# Clock_1.net
KiCad netlist of a schematic drawn in EAGLE
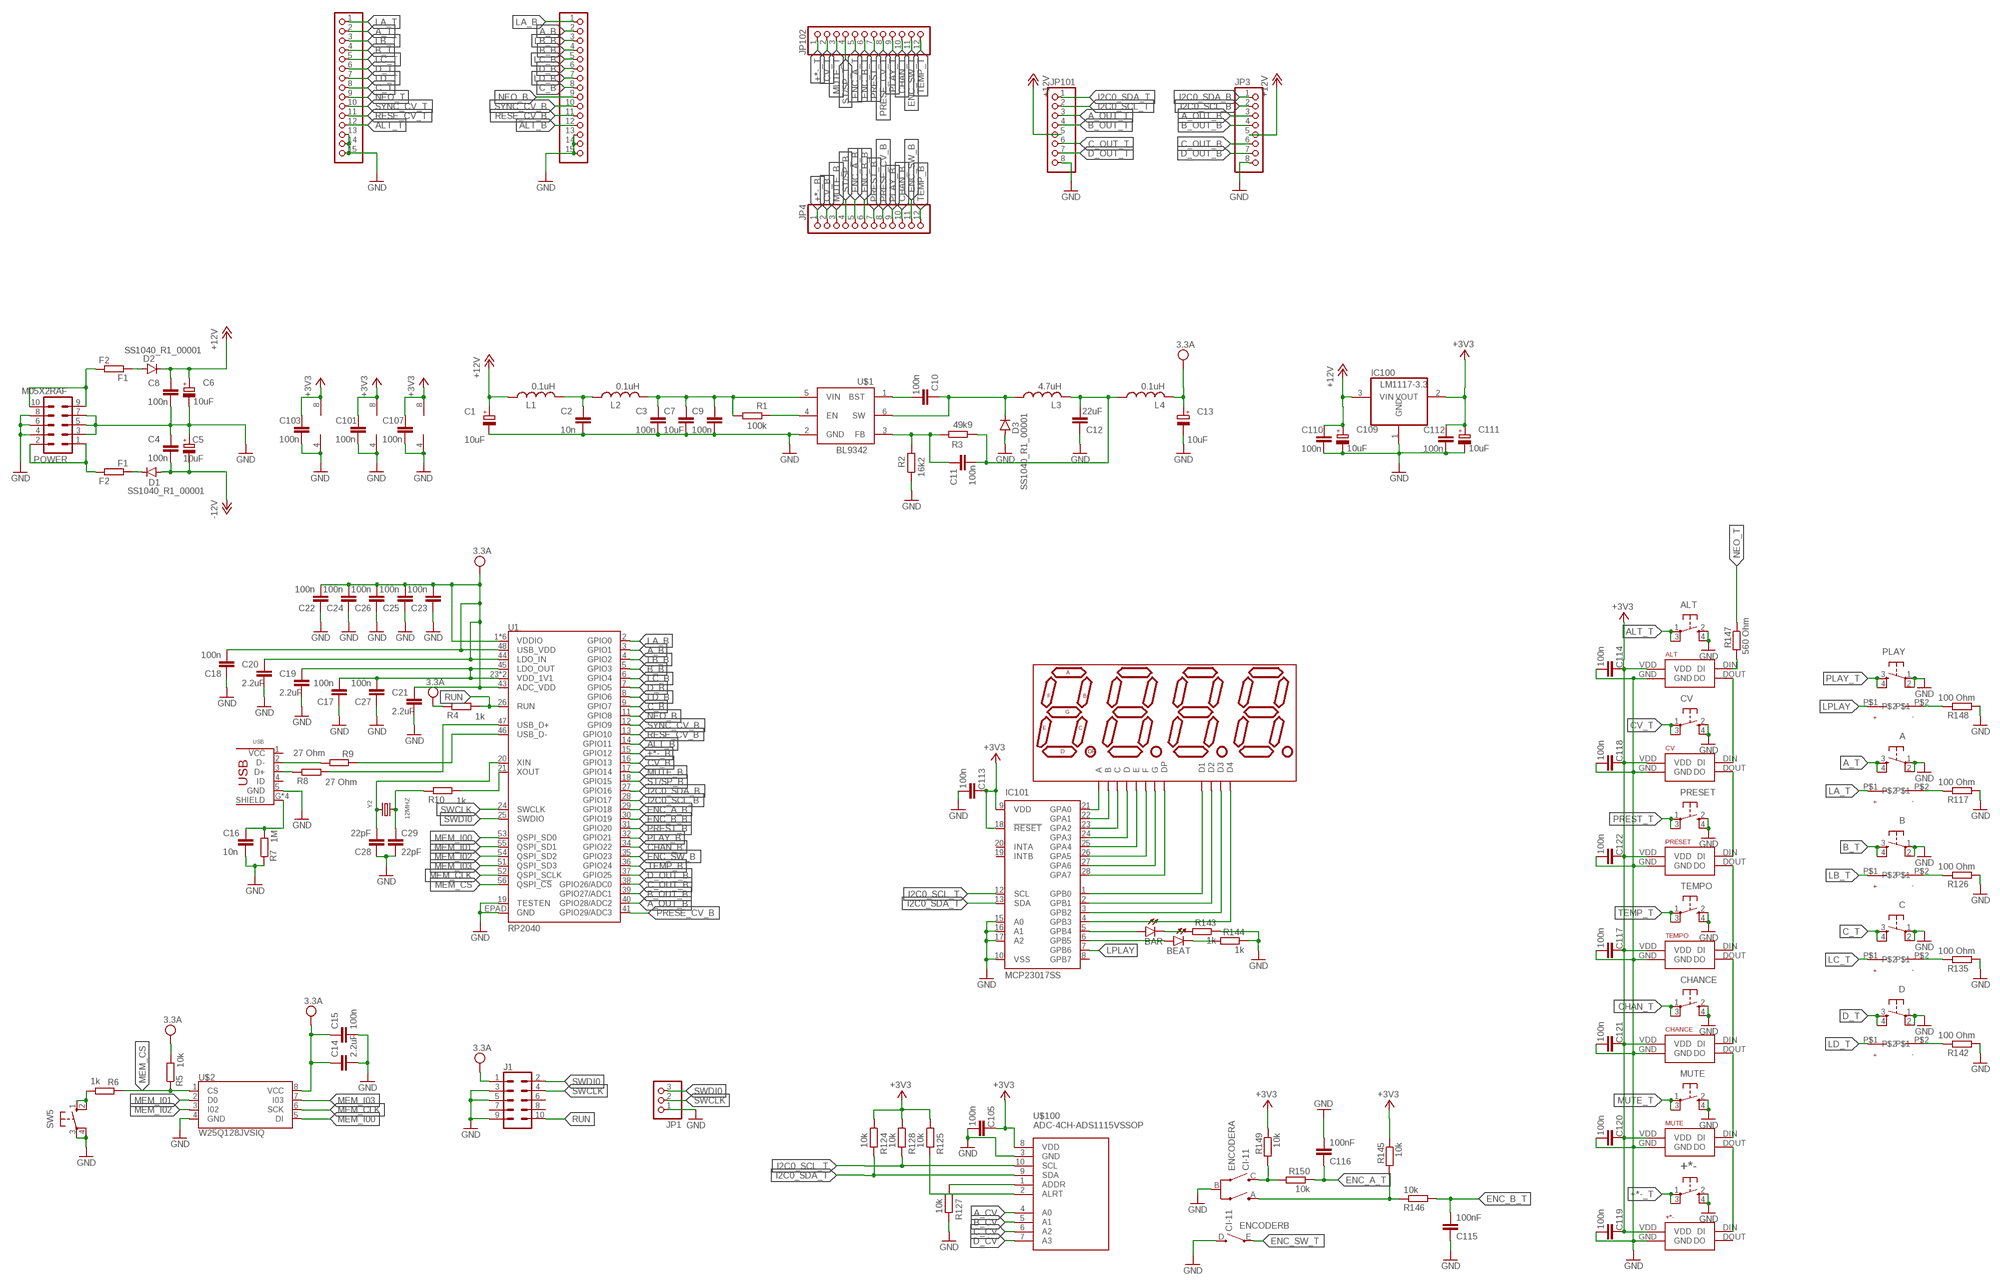
[diagram p0: schematic, sheet 1, part 1 of 2]
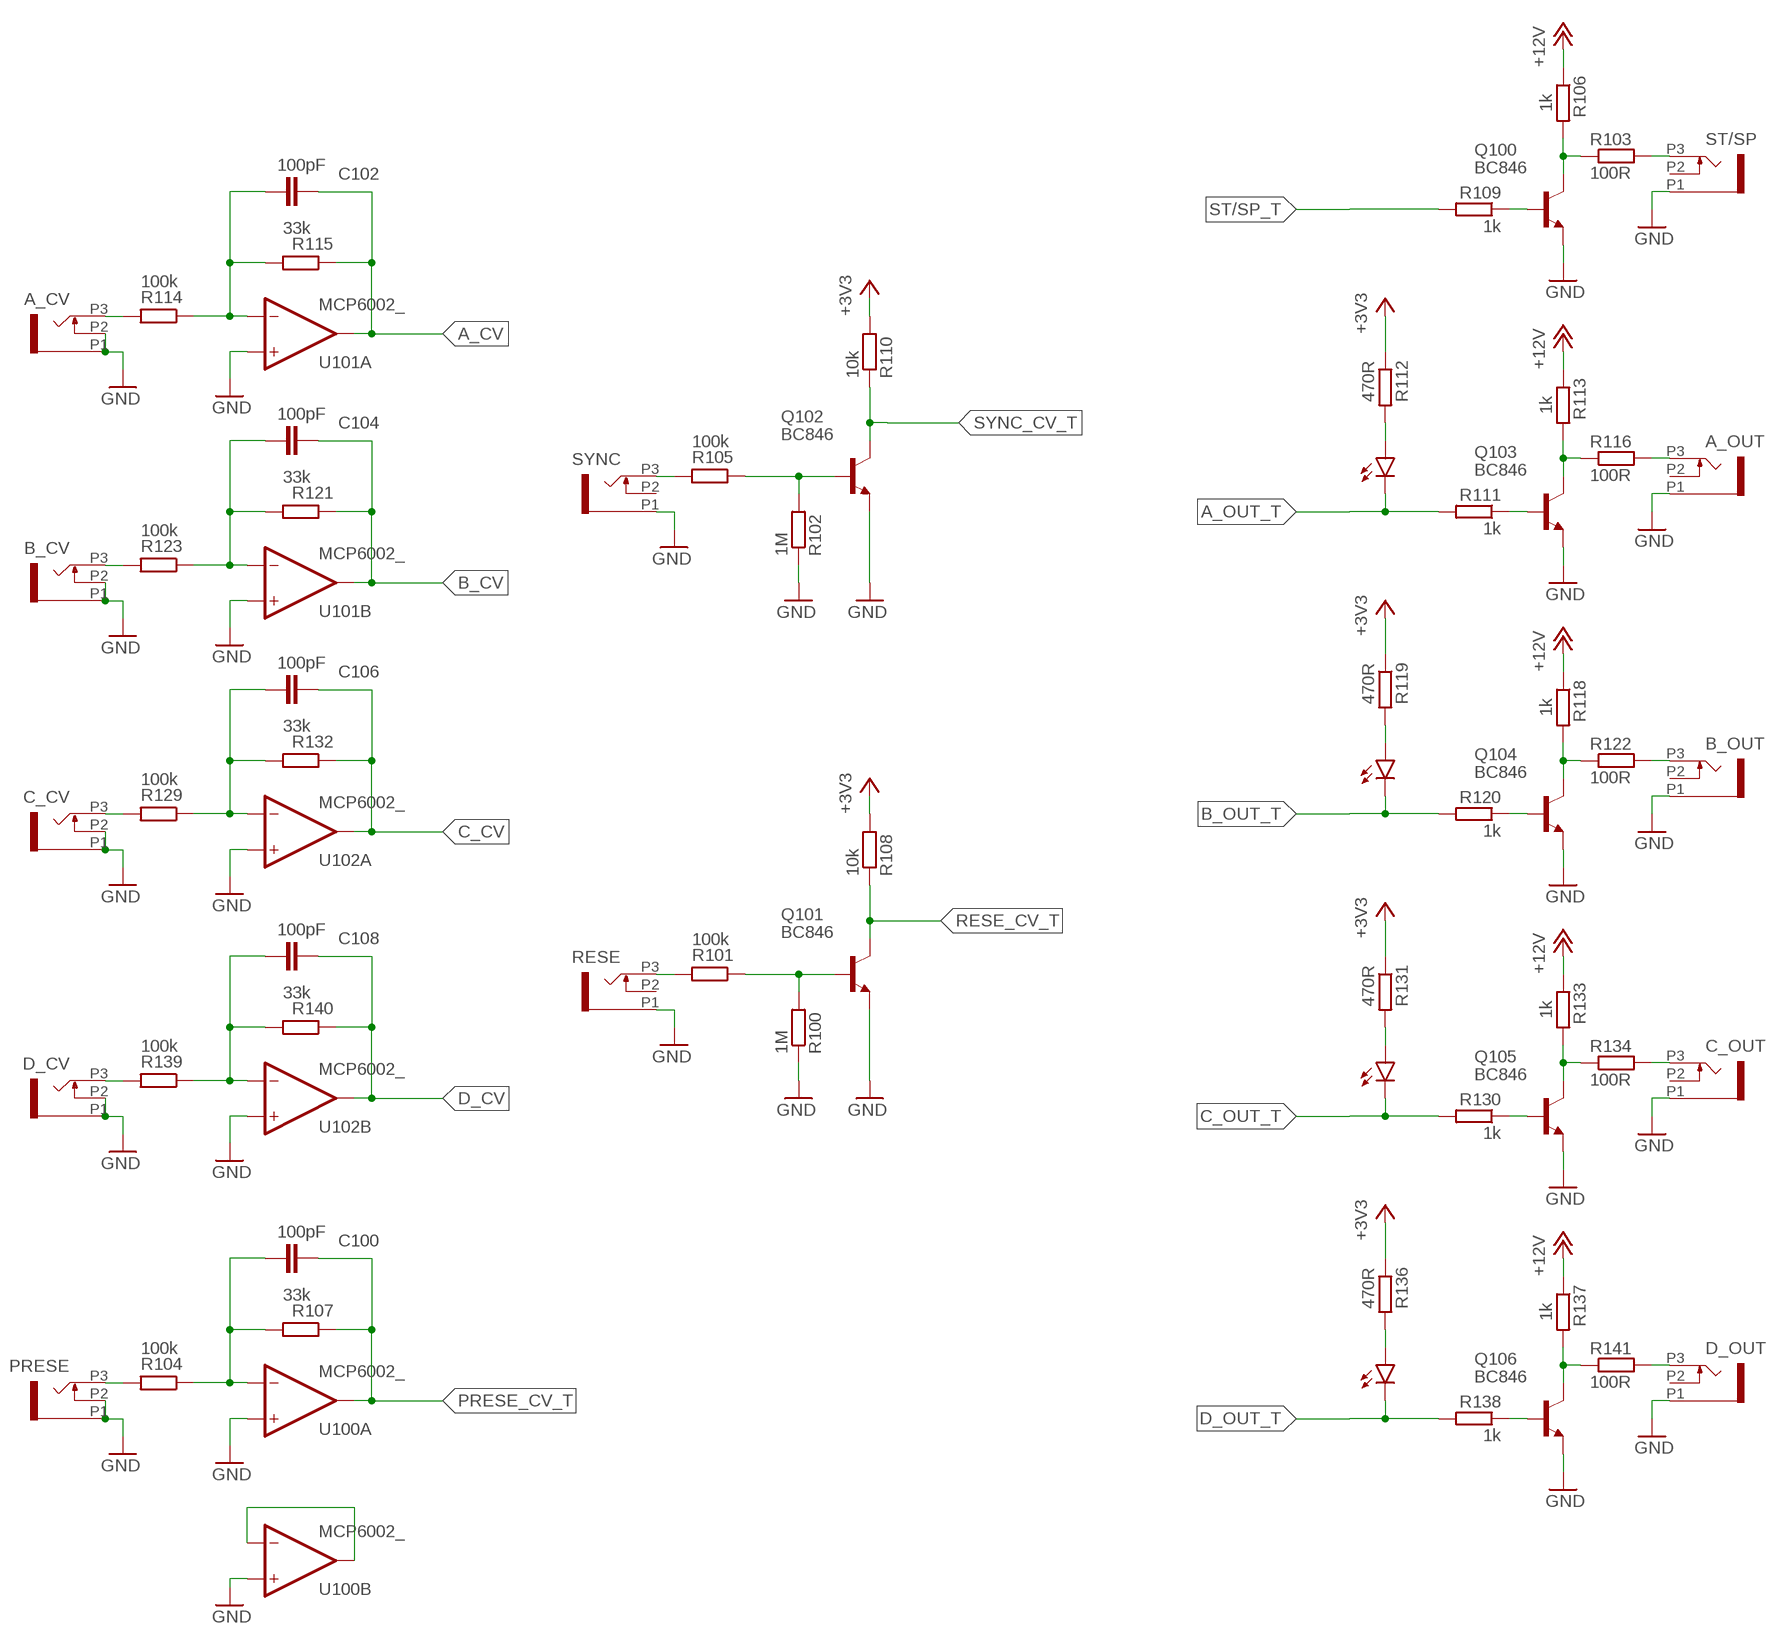
[diagram p1: schematic, sheet 1, part 2 of 2]

(export (version "E")
  (design (tool "Eeschema 10.0.6"))
  (components
    (comp (ref "+*-")
      (value "BUTTON_NEOPIXELBUTTON_PIXEL_ç")
      (footprint "eagle-import:BUTTON_PIXEL_ç")
      (libsource (lib "eagle-import") (part "BUTTON_NEOPIXELBUTTON_PIXEL_ç"))
    )
    (comp (ref "A")
      (value "DTS-6_LEDTME")
      (footprint "eagle-import:TMEBUTTON")
      (libsource (lib "eagle-import") (part "DTS-6_LEDTME"))
    )
    (comp (ref "ALT")
      (value "BUTTON_NEOPIXELBUTTON_PIXEL_ç")
      (footprint "eagle-import:BUTTON_PIXEL_ç")
      (libsource (lib "eagle-import") (part "BUTTON_NEOPIXELBUTTON_PIXEL_ç"))
    )
    (comp (ref "A_CV")
      (value "OG-PJ301_PJ301_THONKICONNNOHOLER")
      (footprint "eagle-import:NOHOLER_GND_SHORT_PADMINI_GND")
      (libsource (lib "eagle-import") (part "OG-PJ301_PJ301_THONKICONNNOHOLER_GND_SHORT_PADMINI_GND"))
    )
    (comp (ref "A_OUT")
      (value "OG-PJ301_PJ301_THONKICONNNOHOLER")
      (footprint "eagle-import:NOHOLER_GND_SHORT_PADMINI_GND")
      (libsource (lib "eagle-import") (part "OG-PJ301_PJ301_THONKICONNNOHOLER_GND_SHORT_PADMINI_GND"))
    )
    (comp (ref "B")
      (value "DTS-6_LEDTME")
      (footprint "eagle-import:TMEBUTTON")
      (libsource (lib "eagle-import") (part "DTS-6_LEDTME"))
    )
    (comp (ref "BAR")
      (value "2 MM LED")
      (footprint "eagle-import:LED3MM")
      (libsource (lib "eagle-import") (part "LED3MM"))
    )
    (comp (ref "BEAT")
      (value "2 MM LED")
      (footprint "eagle-import:LED3MM")
      (libsource (lib "eagle-import") (part "LED3MM"))
    )
    (comp (ref "B_CV")
      (value "OG-PJ301_PJ301_THONKICONNNOHOLER")
      (footprint "eagle-import:NOHOLER_GND_SHORT_PADMINI_GND")
      (libsource (lib "eagle-import") (part "OG-PJ301_PJ301_THONKICONNNOHOLER_GND_SHORT_PADMINI_GND"))
    )
    (comp (ref "B_OUT")
      (value "OG-PJ301_PJ301_THONKICONNNOHOLER")
      (footprint "eagle-import:NOHOLER_GND_SHORT_PADMINI_GND")
      (libsource (lib "eagle-import") (part "OG-PJ301_PJ301_THONKICONNNOHOLER_GND_SHORT_PADMINI_GND"))
    )
    (comp (ref "C")
      (value "DTS-6_LEDTME")
      (footprint "eagle-import:TMEBUTTON")
      (libsource (lib "eagle-import") (part "DTS-6_LEDTME"))
    )
    (comp (ref "C1")
      (value "10uF")
      (footprint "eagle-import:PANASONIC_B")
      (libsource (lib "eagle-import") (part "CPOL-EUB"))
    )
    (comp (ref "C2")
      (value "10n")
      (footprint "eagle-import:C0603")
      (libsource (lib "eagle-import") (part "C-EUC0603"))
    )
    (comp (ref "C3")
      (value "100n")
      (footprint "eagle-import:C0603")
      (libsource (lib "eagle-import") (part "C-EUC0603"))
    )
    (comp (ref "C4")
      (value "100n")
      (footprint "eagle-import:C0603")
      (libsource (lib "eagle-import") (part "C-EUC0603"))
    )
    (comp (ref "C5")
      (value "10uF")
      (footprint "eagle-import:PANASONIC_B")
      (libsource (lib "eagle-import") (part "CPOL-EUB"))
    )
    (comp (ref "C6")
      (value "10uF")
      (footprint "eagle-import:PANASONIC_B")
      (libsource (lib "eagle-import") (part "CPOL-EUB"))
    )
    (comp (ref "C7")
      (value "10uF")
      (footprint "eagle-import:C0603")
      (libsource (lib "eagle-import") (part "C-EUC0603"))
    )
    (comp (ref "C8")
      (value "100n")
      (footprint "eagle-import:C0603")
      (libsource (lib "eagle-import") (part "C-EUC0603"))
    )
    (comp (ref "C9")
      (value "100n")
      (footprint "eagle-import:C0603")
      (libsource (lib "eagle-import") (part "C-EUC0603"))
    )
    (comp (ref "C10")
      (value "100n")
      (footprint "eagle-import:C0603")
      (libsource (lib "eagle-import") (part "C-EUC0603"))
    )
    (comp (ref "C11")
      (value "100n")
      (footprint "eagle-import:C0603")
      (libsource (lib "eagle-import") (part "C-EUC0603"))
    )
    (comp (ref "C12")
      (value "22uF")
      (footprint "eagle-import:C0603")
      (libsource (lib "eagle-import") (part "C-EUC0603"))
    )
    (comp (ref "C13")
      (value "10uF")
      (footprint "eagle-import:PANASONIC_B")
      (libsource (lib "eagle-import") (part "CPOL-EUB"))
    )
    (comp (ref "C14")
      (value "2.2uF")
      (footprint "eagle-import:C0603")
      (libsource (lib "eagle-import") (part "C-EUC0603"))
    )
    (comp (ref "C15")
      (value "100n")
      (footprint "eagle-import:C0603")
      (libsource (lib "eagle-import") (part "C-EUC0603"))
    )
    (comp (ref "C16")
      (value "10n")
      (footprint "eagle-import:C0603")
      (libsource (lib "eagle-import") (part "C-EUC0603"))
    )
    (comp (ref "C17")
      (value "100n")
      (footprint "eagle-import:C0603")
      (libsource (lib "eagle-import") (part "C-EUC0603"))
    )
    (comp (ref "C18")
      (value "100n")
      (footprint "eagle-import:C0603")
      (libsource (lib "eagle-import") (part "C-EUC0603"))
    )
    (comp (ref "C19")
      (value "2.2uF")
      (footprint "eagle-import:C0603")
      (libsource (lib "eagle-import") (part "C-EUC0603"))
    )
    (comp (ref "C20")
      (value "2.2uF")
      (footprint "eagle-import:C0603")
      (libsource (lib "eagle-import") (part "C-EUC0603"))
    )
    (comp (ref "C21")
      (value "2.2uF")
      (footprint "eagle-import:C0603")
      (libsource (lib "eagle-import") (part "C-EUC0603"))
    )
    (comp (ref "C22")
      (value "100n")
      (footprint "eagle-import:C0603")
      (libsource (lib "eagle-import") (part "C-EUC0603"))
    )
    (comp (ref "C23")
      (value "100n")
      (footprint "eagle-import:C0603")
      (libsource (lib "eagle-import") (part "C-EUC0603"))
    )
    (comp (ref "C24")
      (value "100n")
      (footprint "eagle-import:C0603")
      (libsource (lib "eagle-import") (part "C-EUC0603"))
    )
    (comp (ref "C25")
      (value "100n")
      (footprint "eagle-import:C0603")
      (libsource (lib "eagle-import") (part "C-EUC0603"))
    )
    (comp (ref "C26")
      (value "100n")
      (footprint "eagle-import:C0603")
      (libsource (lib "eagle-import") (part "C-EUC0603"))
    )
    (comp (ref "C27")
      (value "100n")
      (footprint "eagle-import:C0603")
      (libsource (lib "eagle-import") (part "C-EUC0603"))
    )
    (comp (ref "C28")
      (value "22pF")
      (footprint "eagle-import:C0603")
      (libsource (lib "eagle-import") (part "C-EUC0603"))
    )
    (comp (ref "C29")
      (value "22pF")
      (footprint "eagle-import:C0603")
      (libsource (lib "eagle-import") (part "C-EUC0603"))
    )
    (comp (ref "C100")
      (value "100pF")
      (footprint "eagle-import:C0603")
      (libsource (lib "eagle-import") (part "rcl_334_C-EUC0603"))
    )
    (comp (ref "C101")
      (value "100n")
      (footprint "eagle-import:C0603")
      (libsource (lib "eagle-import") (part "C-EUC0603"))
    )
    (comp (ref "C102")
      (value "100pF")
      (footprint "eagle-import:C0603")
      (libsource (lib "eagle-import") (part "rcl_334_C-EUC0603"))
    )
    (comp (ref "C103")
      (value "100n")
      (footprint "eagle-import:C0603")
      (libsource (lib "eagle-import") (part "C-EUC0603"))
    )
    (comp (ref "C104")
      (value "100pF")
      (footprint "eagle-import:C0603")
      (libsource (lib "eagle-import") (part "rcl_334_C-EUC0603"))
    )
    (comp (ref "C105")
      (value "100n")
      (footprint "eagle-import:C0603")
      (libsource (lib "eagle-import") (part "C-EUC0603"))
    )
    (comp (ref "C106")
      (value "100pF")
      (footprint "eagle-import:C0603")
      (libsource (lib "eagle-import") (part "rcl_334_C-EUC0603"))
    )
    (comp (ref "C107")
      (value "100n")
      (footprint "eagle-import:C0603")
      (libsource (lib "eagle-import") (part "C-EUC0603"))
    )
    (comp (ref "C108")
      (value "100pF")
      (footprint "eagle-import:C0603")
      (libsource (lib "eagle-import") (part "rcl_334_C-EUC0603"))
    )
    (comp (ref "C109")
      (value "10uF")
      (footprint "eagle-import:PANASONIC_B")
      (libsource (lib "eagle-import") (part "CPOL-EUB"))
    )
    (comp (ref "C110")
      (value "100n")
      (footprint "eagle-import:C0603")
      (libsource (lib "eagle-import") (part "C-EUC0603"))
    )
    (comp (ref "C111")
      (value "10uF")
      (footprint "eagle-import:PANASONIC_B")
      (libsource (lib "eagle-import") (part "CPOL-EUB"))
    )
    (comp (ref "C112")
      (value "100n")
      (footprint "eagle-import:C0603")
      (libsource (lib "eagle-import") (part "C-EUC0603"))
    )
    (comp (ref "C113")
      (value "100n")
      (footprint "eagle-import:C0603")
      (libsource (lib "eagle-import") (part "C-EUC0603"))
    )
    (comp (ref "C114")
      (value "100n")
      (footprint "eagle-import:C0603")
      (libsource (lib "eagle-import") (part "C-EUC0603"))
    )
    (comp (ref "C115")
      (value "100nF")
      (footprint "eagle-import:C0603")
      (libsource (lib "eagle-import") (part "rcl_334_C-EUC0603"))
    )
    (comp (ref "C116")
      (value "100nF")
      (footprint "eagle-import:C0603")
      (libsource (lib "eagle-import") (part "rcl_334_C-EUC0603"))
    )
    (comp (ref "C117")
      (value "100n")
      (footprint "eagle-import:C0603")
      (libsource (lib "eagle-import") (part "C-EUC0603"))
    )
    (comp (ref "C118")
      (value "100n")
      (footprint "eagle-import:C0603")
      (libsource (lib "eagle-import") (part "C-EUC0603"))
    )
    (comp (ref "C119")
      (value "100n")
      (footprint "eagle-import:C0603")
      (libsource (lib "eagle-import") (part "C-EUC0603"))
    )
    (comp (ref "C120")
      (value "100n")
      (footprint "eagle-import:C0603")
      (libsource (lib "eagle-import") (part "C-EUC0603"))
    )
    (comp (ref "C121")
      (value "100n")
      (footprint "eagle-import:C0603")
      (libsource (lib "eagle-import") (part "C-EUC0603"))
    )
    (comp (ref "C122")
      (value "100n")
      (footprint "eagle-import:C0603")
      (libsource (lib "eagle-import") (part "C-EUC0603"))
    )
    (comp (ref "CHANCE")
      (value "BUTTON_NEOPIXELBUTTON_PIXEL_ç")
      (footprint "eagle-import:BUTTON_PIXEL_ç")
      (libsource (lib "eagle-import") (part "BUTTON_NEOPIXELBUTTON_PIXEL_ç"))
    )
    (comp (ref "CV")
      (value "BUTTON_NEOPIXELBUTTON_PIXEL_ç")
      (footprint "eagle-import:BUTTON_PIXEL_ç")
      (libsource (lib "eagle-import") (part "BUTTON_NEOPIXELBUTTON_PIXEL_ç"))
    )
    (comp (ref "C_CV")
      (value "OG-PJ301_PJ301_THONKICONNNOHOLER")
      (footprint "eagle-import:NOHOLER_GND_SHORT_PADMINI_GND")
      (libsource (lib "eagle-import") (part "OG-PJ301_PJ301_THONKICONNNOHOLER_GND_SHORT_PADMINI_GND"))
    )
    (comp (ref "C_OUT")
      (value "OG-PJ301_PJ301_THONKICONNNOHOLER")
      (footprint "eagle-import:NOHOLER_GND_SHORT_PADMINI_GND")
      (libsource (lib "eagle-import") (part "OG-PJ301_PJ301_THONKICONNNOHOLER_GND_SHORT_PADMINI_GND"))
    )
    (comp (ref "D")
      (value "DTS-6_LEDTME")
      (footprint "eagle-import:TMEBUTTON")
      (libsource (lib "eagle-import") (part "DTS-6_LEDTME"))
    )
    (comp (ref "D1")
      (value "SS1040_R1_00001")
      (footprint "eagle-import:SOD123")
      (libsource (lib "eagle-import") (part "DIODE-SOD123"))
    )
    (comp (ref "D2")
      (value "SS1040_R1_00001")
      (footprint "eagle-import:SOD123")
      (libsource (lib "eagle-import") (part "DIODE-SOD123"))
    )
    (comp (ref "D3")
      (value "SS1040_R1_00001")
      (footprint "eagle-import:SOD123")
      (libsource (lib "eagle-import") (part "DIODE-SOD123"))
    )
    (comp (ref "D_CV")
      (value "OG-PJ301_PJ301_THONKICONNNOHOLER")
      (footprint "eagle-import:NOHOLER_GND_SHORT_PADMINI_GND")
      (libsource (lib "eagle-import") (part "OG-PJ301_PJ301_THONKICONNNOHOLER_GND_SHORT_PADMINI_GND"))
    )
    (comp (ref "D_OUT")
      (value "OG-PJ301_PJ301_THONKICONNNOHOLER")
      (footprint "eagle-import:NOHOLER_GND_SHORT_PADMINI_GND")
      (libsource (lib "eagle-import") (part "OG-PJ301_PJ301_THONKICONNNOHOLER_GND_SHORT_PADMINI_GND"))
    )
    (comp (ref "ENCODER")
      (value "CI-11")
      (footprint "eagle-import:CI-11")
      (libsource (lib "eagle-import") (part "CI-11"))
    )
    (comp (ref "F1")
      (value "F2")
      (footprint "eagle-import:R0603")
      (libsource (lib "eagle-import") (part "R-EU_R0603"))
    )
    (comp (ref "F2")
      (value "F1")
      (footprint "eagle-import:R0603")
      (libsource (lib "eagle-import") (part "R-EU_R0603"))
    )
    (comp (ref "IC100")
      (value "LM1117-3.3")
      (footprint "eagle-import:SOT223")
      (libsource (lib "eagle-import") (part "REG1117"))
    )
    (comp (ref "IC101")
      (value "MCP23017SS")
      (footprint "eagle-import:SSOP28")
      (libsource (lib "eagle-import") (part "MCP23017SS"))
    )
    (comp (ref "J1")
      (value "CONN_05X2RA")
      (footprint "eagle-import:2X5-RA")
      (libsource (lib "eagle-import") (part "CONN_05X2RA"))
    )
    (comp (ref "JP1")
      (value "PINHD-1X31X3*")
      (footprint "eagle-import:1X3_")
      (libsource (lib "eagle-import") (part "PINHD-1X31X3"))
    )
    (comp (ref "JP2")
      (value "PINHD-1X151X15ç")
      (footprint "eagle-import:1X15ç")
      (libsource (lib "eagle-import") (part "PINHD-1X151X15ç"))
    )
    (comp (ref "JP3")
      (value "PINHD-1X81X8ç")
      (footprint "eagle-import:1X8ç")
      (libsource (lib "eagle-import") (part "PINHD-1X81X8ç"))
    )
    (comp (ref "JP4")
      (value "PINHD-1X12Ç")
      (footprint "eagle-import:1X12Ç")
      (libsource (lib "eagle-import") (part "PINHD-1X12Ç"))
    )
    (comp (ref "JP100")
      (value "PINHD-1X151X15ç")
      (footprint "eagle-import:1X15ç")
      (libsource (lib "eagle-import") (part "PINHD-1X151X15ç"))
    )
    (comp (ref "JP101")
      (value "PINHD-1X81X8ç")
      (footprint "eagle-import:1X8ç")
      (libsource (lib "eagle-import") (part "PINHD-1X81X8ç"))
    )
    (comp (ref "JP102")
      (value "PINHD-1X12Ç")
      (footprint "eagle-import:1X12Ç")
      (libsource (lib "eagle-import") (part "PINHD-1X12Ç"))
    )
    (comp (ref "L1")
      (value "0.1uH")
      (footprint "eagle-import:L3225P")
      (libsource (lib "eagle-import") (part "L-USL3225P"))
    )
    (comp (ref "L2")
      (value "0.1uH")
      (footprint "eagle-import:L3225P")
      (libsource (lib "eagle-import") (part "L-USL3225P"))
    )
    (comp (ref "L3")
      (value "4.7uH")
      (footprint "eagle-import:L3225P")
      (libsource (lib "eagle-import") (part "L-USL3225P"))
    )
    (comp (ref "L4")
      (value "0.1uH")
      (footprint "eagle-import:L3225P")
      (libsource (lib "eagle-import") (part "L-USL3225P"))
    )
    (comp (ref "LED_A_OUT")
      (value "2 MM LED")
      (footprint "eagle-import:LED3MM")
      (libsource (lib "eagle-import") (part "LED3MM"))
    )
    (comp (ref "LED_B_OUT")
      (value "2 MM LED")
      (footprint "eagle-import:LED3MM")
      (libsource (lib "eagle-import") (part "LED3MM"))
    )
    (comp (ref "LED_C_OUT")
      (value "2 MM LED")
      (footprint "eagle-import:LED3MM")
      (libsource (lib "eagle-import") (part "LED3MM"))
    )
    (comp (ref "LED_D_OUT")
      (value "2 MM LED")
      (footprint "eagle-import:LED3MM")
      (libsource (lib "eagle-import") (part "LED3MM"))
    )
    (comp (ref "LFD36BUE-101B")
      (value "7-SEGMENT-4DIGIT-20MM")
      (footprint "eagle-import:7-SEGMENT-4DIGIT-30MM")
      (libsource (lib "eagle-import") (part "7-SEGMENT-4DIGIT-20MM"))
    )
    (comp (ref "MUTE")
      (value "BUTTON_NEOPIXELBUTTON_PIXEL_ç")
      (footprint "eagle-import:BUTTON_PIXEL_ç")
      (libsource (lib "eagle-import") (part "BUTTON_NEOPIXELBUTTON_PIXEL_ç"))
    )
    (comp (ref "PLAY")
      (value "DTS-6_LED")
      (footprint "eagle-import:TIMEBUTTON_HOLES_LEDS")
      (libsource (lib "eagle-import") (part "DTS-6_LED"))
    )
    (comp (ref "POWER")
      (value "M05X2RAF")
      (footprint "eagle-import:2X5-POWER_ACODADO")
      (libsource (lib "eagle-import") (part "M05X2RAF"))
    )
    (comp (ref "PRESE")
      (value "OG-PJ301_PJ301_THONKICONNNOHOLER")
      (footprint "eagle-import:NOHOLER_GND_SHORT_PADMINI_GND")
      (libsource (lib "eagle-import") (part "OG-PJ301_PJ301_THONKICONNNOHOLER_GND_SHORT_PADMINI_GND"))
    )
    (comp (ref "PRESET")
      (value "BUTTON_NEOPIXELBUTTON_PIXEL_ç")
      (footprint "eagle-import:BUTTON_PIXEL_ç")
      (libsource (lib "eagle-import") (part "BUTTON_NEOPIXELBUTTON_PIXEL_ç"))
    )
    (comp (ref "Q100")
      (value "BC846")
      (footprint "eagle-import:SOT23")
      (libsource (lib "eagle-import") (part "BC846"))
    )
    (comp (ref "Q101")
      (value "BC846")
      (footprint "eagle-import:SOT23")
      (libsource (lib "eagle-import") (part "BC846"))
    )
    (comp (ref "Q102")
      (value "BC846")
      (footprint "eagle-import:SOT23")
      (libsource (lib "eagle-import") (part "BC846"))
    )
    (comp (ref "Q103")
      (value "BC846")
      (footprint "eagle-import:SOT23")
      (libsource (lib "eagle-import") (part "BC846"))
    )
    (comp (ref "Q104")
      (value "BC846")
      (footprint "eagle-import:SOT23")
      (libsource (lib "eagle-import") (part "BC846"))
    )
    (comp (ref "Q105")
      (value "BC846")
      (footprint "eagle-import:SOT23")
      (libsource (lib "eagle-import") (part "BC846"))
    )
    (comp (ref "Q106")
      (value "BC846")
      (footprint "eagle-import:SOT23")
      (libsource (lib "eagle-import") (part "BC846"))
    )
    (comp (ref "R1")
      (value "100k")
      (footprint "eagle-import:R0603")
      (libsource (lib "eagle-import") (part "R-EU_R0603"))
    )
    (comp (ref "R2")
      (value "16k2")
      (footprint "eagle-import:R0603")
      (libsource (lib "eagle-import") (part "R-EU_R0603"))
    )
    (comp (ref "R3")
      (value "49k9")
      (footprint "eagle-import:R0603")
      (libsource (lib "eagle-import") (part "R-EU_R0603"))
    )
    (comp (ref "R4")
      (value "1k")
      (footprint "eagle-import:R0603")
      (libsource (lib "eagle-import") (part "R-EU_R0603"))
    )
    (comp (ref "R5")
      (value "10k")
      (footprint "eagle-import:R0603")
      (libsource (lib "eagle-import") (part "R-EU_R0603"))
    )
    (comp (ref "R6")
      (value "1k")
      (footprint "eagle-import:R0603")
      (libsource (lib "eagle-import") (part "R-EU_R0603"))
    )
    (comp (ref "R7")
      (value "1M")
      (footprint "eagle-import:R0603")
      (libsource (lib "eagle-import") (part "R-EU_R0603"))
    )
    (comp (ref "R8")
      (value "27 Ohm")
      (footprint "eagle-import:R0603")
      (libsource (lib "eagle-import") (part "R-EU_R0603"))
    )
    (comp (ref "R9")
      (value "27 Ohm")
      (footprint "eagle-import:R0603")
      (libsource (lib "eagle-import") (part "R-EU_R0603"))
    )
    (comp (ref "R10")
      (value "1k")
      (footprint "eagle-import:R0603")
      (libsource (lib "eagle-import") (part "R-EU_R0603"))
    )
    (comp (ref "R100")
      (value "1M")
      (footprint "eagle-import:R0603")
      (libsource (lib "eagle-import") (part "R-EU_R0603"))
    )
    (comp (ref "R101")
      (value "100k")
      (footprint "eagle-import:R0603")
      (libsource (lib "eagle-import") (part "R-EU_R0603"))
    )
    (comp (ref "R102")
      (value "1M")
      (footprint "eagle-import:R0603")
      (libsource (lib "eagle-import") (part "R-EU_R0603"))
    )
    (comp (ref "R103")
      (value "100R")
      (footprint "eagle-import:R0603")
      (libsource (lib "eagle-import") (part "R-EU_R0603"))
    )
    (comp (ref "R104")
      (value "100k")
      (footprint "eagle-import:R0603")
      (libsource (lib "eagle-import") (part "R-EU_R0603"))
    )
    (comp (ref "R105")
      (value "100k")
      (footprint "eagle-import:R0603")
      (libsource (lib "eagle-import") (part "R-EU_R0603"))
    )
    (comp (ref "R106")
      (value "1k")
      (footprint "eagle-import:R0603")
      (libsource (lib "eagle-import") (part "R-EU_R0603"))
    )
    (comp (ref "R107")
      (value "33k")
      (footprint "eagle-import:R0603")
      (libsource (lib "eagle-import") (part "R-EU_R0603"))
    )
    (comp (ref "R108")
      (value "10k")
      (footprint "eagle-import:R0603")
      (libsource (lib "eagle-import") (part "R-EU_R0603"))
    )
    (comp (ref "R109")
      (value "1k")
      (footprint "eagle-import:R0603")
      (libsource (lib "eagle-import") (part "R-EU_R0603"))
    )
    (comp (ref "R110")
      (value "10k")
      (footprint "eagle-import:R0603")
      (libsource (lib "eagle-import") (part "R-EU_R0603"))
    )
    (comp (ref "R111")
      (value "1k")
      (footprint "eagle-import:R0603")
      (libsource (lib "eagle-import") (part "R-EU_R0603"))
    )
    (comp (ref "R112")
      (value "470R")
      (footprint "eagle-import:R0603")
      (libsource (lib "eagle-import") (part "R-EU_R0603"))
    )
    (comp (ref "R113")
      (value "1k")
      (footprint "eagle-import:R0603")
      (libsource (lib "eagle-import") (part "R-EU_R0603"))
    )
    (comp (ref "R114")
      (value "100k")
      (footprint "eagle-import:R0603")
      (libsource (lib "eagle-import") (part "R-EU_R0603"))
    )
    (comp (ref "R115")
      (value "33k")
      (footprint "eagle-import:R0603")
      (libsource (lib "eagle-import") (part "R-EU_R0603"))
    )
    (comp (ref "R116")
      (value "100R")
      (footprint "eagle-import:R0603")
      (libsource (lib "eagle-import") (part "R-EU_R0603"))
    )
    (comp (ref "R117")
      (value "100 Ohm")
      (footprint "eagle-import:R0603")
      (libsource (lib "eagle-import") (part "R-EU_R0603"))
    )
    (comp (ref "R118")
      (value "1k")
      (footprint "eagle-import:R0603")
      (libsource (lib "eagle-import") (part "R-EU_R0603"))
    )
    (comp (ref "R119")
      (value "470R")
      (footprint "eagle-import:R0603")
      (libsource (lib "eagle-import") (part "R-EU_R0603"))
    )
    (comp (ref "R120")
      (value "1k")
      (footprint "eagle-import:R0603")
      (libsource (lib "eagle-import") (part "R-EU_R0603"))
    )
    (comp (ref "R121")
      (value "33k")
      (footprint "eagle-import:R0603")
      (libsource (lib "eagle-import") (part "R-EU_R0603"))
    )
    (comp (ref "R122")
      (value "100R")
      (footprint "eagle-import:R0603")
      (libsource (lib "eagle-import") (part "R-EU_R0603"))
    )
    (comp (ref "R123")
      (value "100k")
      (footprint "eagle-import:R0603")
      (libsource (lib "eagle-import") (part "R-EU_R0603"))
    )
    (comp (ref "R124")
      (value "10k")
      (footprint "eagle-import:R0603")
      (libsource (lib "eagle-import") (part "R-EU_R0603"))
    )
    (comp (ref "R125")
      (value "10k")
      (footprint "eagle-import:R0603")
      (libsource (lib "eagle-import") (part "R-EU_R0603"))
    )
    (comp (ref "R126")
      (value "100 Ohm")
      (footprint "eagle-import:R0603")
      (libsource (lib "eagle-import") (part "R-EU_R0603"))
    )
    (comp (ref "R127")
      (value "10k")
      (footprint "eagle-import:R0603")
      (libsource (lib "eagle-import") (part "R-EU_R0603"))
    )
    (comp (ref "R128")
      (value "10k")
      (footprint "eagle-import:R0603")
      (libsource (lib "eagle-import") (part "R-EU_R0603"))
    )
    (comp (ref "R129")
      (value "100k")
      (footprint "eagle-import:R0603")
      (libsource (lib "eagle-import") (part "R-EU_R0603"))
    )
    (comp (ref "R130")
      (value "1k")
      (footprint "eagle-import:R0603")
      (libsource (lib "eagle-import") (part "R-EU_R0603"))
    )
    (comp (ref "R131")
      (value "470R")
      (footprint "eagle-import:R0603")
      (libsource (lib "eagle-import") (part "R-EU_R0603"))
    )
    (comp (ref "R132")
      (value "33k")
      (footprint "eagle-import:R0603")
      (libsource (lib "eagle-import") (part "R-EU_R0603"))
    )
    (comp (ref "R133")
      (value "1k")
      (footprint "eagle-import:R0603")
      (libsource (lib "eagle-import") (part "R-EU_R0603"))
    )
    (comp (ref "R134")
      (value "100R")
      (footprint "eagle-import:R0603")
      (libsource (lib "eagle-import") (part "R-EU_R0603"))
    )
    (comp (ref "R135")
      (value "100 Ohm")
      (footprint "eagle-import:R0603")
      (libsource (lib "eagle-import") (part "R-EU_R0603"))
    )
    (comp (ref "R136")
      (value "470R")
      (footprint "eagle-import:R0603")
      (libsource (lib "eagle-import") (part "R-EU_R0603"))
    )
    (comp (ref "R137")
      (value "1k")
      (footprint "eagle-import:R0603")
      (libsource (lib "eagle-import") (part "R-EU_R0603"))
    )
    (comp (ref "R138")
      (value "1k")
      (footprint "eagle-import:R0603")
      (libsource (lib "eagle-import") (part "R-EU_R0603"))
    )
    (comp (ref "R139")
      (value "100k")
      (footprint "eagle-import:R0603")
      (libsource (lib "eagle-import") (part "R-EU_R0603"))
    )
    (comp (ref "R140")
      (value "33k")
      (footprint "eagle-import:R0603")
      (libsource (lib "eagle-import") (part "R-EU_R0603"))
    )
    (comp (ref "R141")
      (value "100R")
      (footprint "eagle-import:R0603")
      (libsource (lib "eagle-import") (part "R-EU_R0603"))
    )
    (comp (ref "R142")
      (value "100 Ohm")
      (footprint "eagle-import:R0603")
      (libsource (lib "eagle-import") (part "R-EU_R0603"))
    )
    (comp (ref "R143")
      (value "1k")
      (footprint "eagle-import:R0603")
      (libsource (lib "eagle-import") (part "R-EU_R0603"))
    )
    (comp (ref "R144")
      (value "1k")
      (footprint "eagle-import:R0603")
      (libsource (lib "eagle-import") (part "R-EU_R0603"))
    )
    (comp (ref "R145")
      (value "10k")
      (footprint "eagle-import:R0603")
      (libsource (lib "eagle-import") (part "rcl_334_R-EU_R0603"))
    )
    (comp (ref "R146")
      (value "10k")
      (footprint "eagle-import:R0603")
      (libsource (lib "eagle-import") (part "rcl_334_R-EU_R0603"))
    )
    (comp (ref "R147")
      (value "560 Ohm")
      (footprint "eagle-import:R0603")
      (libsource (lib "eagle-import") (part "R-EU_R0603"))
    )
    (comp (ref "R148")
      (value "100 Ohm")
      (footprint "eagle-import:R0603")
      (libsource (lib "eagle-import") (part "R-EU_R0603"))
    )
    (comp (ref "R149")
      (value "10k")
      (footprint "eagle-import:R0603")
      (libsource (lib "eagle-import") (part "rcl_334_R-EU_R0603"))
    )
    (comp (ref "R150")
      (value "10k")
      (footprint "eagle-import:R0603")
      (libsource (lib "eagle-import") (part "rcl_334_R-EU_R0603"))
    )
    (comp (ref "RESE")
      (value "OG-PJ301_PJ301_THONKICONNNOHOLER")
      (footprint "eagle-import:NOHOLER_GND_SHORT_PADMINI_GND")
      (libsource (lib "eagle-import") (part "OG-PJ301_PJ301_THONKICONNNOHOLER_GND_SHORT_PADMINI_GND"))
    )
    (comp (ref "ST/SP")
      (value "OG-PJ301_PJ301_THONKICONNNOHOLER")
      (footprint "eagle-import:NOHOLER_GND_SHORT_PADMINI_GND")
      (libsource (lib "eagle-import") (part "OG-PJ301_PJ301_THONKICONNNOHOLER_GND_SHORT_PADMINI_GND"))
    )
    (comp (ref "SW5")
      (value "10-XX")
      (footprint "eagle-import:B3F-10XX")
      (fields (field (name "MPN") "B3F-1000"))
      (libsource (lib "eagle-import") (part "10-XX"))
    )
    (comp (ref "SYNC")
      (value "OG-PJ301_PJ301_THONKICONNNOHOLER")
      (footprint "eagle-import:NOHOLER_GND_SHORT_PADMINI_GND")
      (libsource (lib "eagle-import") (part "OG-PJ301_PJ301_THONKICONNNOHOLER_GND_SHORT_PADMINI_GND"))
    )
    (comp (ref "TEMPO")
      (value "BUTTON_NEOPIXELBUTTON_PIXEL_ç")
      (footprint "eagle-import:BUTTON_PIXEL_ç")
      (libsource (lib "eagle-import") (part "BUTTON_NEOPIXELBUTTON_PIXEL_ç"))
    )
    (comp (ref "U$1")
      (value "BL9342")
      (footprint "eagle-import:SOT23-6")
      (libsource (lib "eagle-import") (part "BL9342"))
    )
    (comp (ref "U$2")
      (value "W25Q128JVSIQ")
      (footprint "eagle-import:SOIC-8")
      (libsource (lib "eagle-import") (part "W25Q128JVSIQ"))
    )
    (comp (ref "U$100")
      (value "ADC-4CH-ADS1115VSSOP")
      (footprint "eagle-import:ADC-4CH-ADS1115-VSSOP")
      (libsource (lib "eagle-import") (part "ADC-4CH-ADS1115VSSOP"))
    )
    (comp (ref "U1")
      (value "RP2040")
      (footprint "eagle-import:QFN-56")
      (libsource (lib "eagle-import") (part "RP2040"))
    )
    (comp (ref "U100")
      (value "MCP6002_")
      (footprint "eagle-import:SO08")
      (libsource (lib "eagle-import") (part "MCP6002_"))
    )
    (comp (ref "U101")
      (value "MCP6002_")
      (footprint "eagle-import:SO08")
      (libsource (lib "eagle-import") (part "MCP6002_"))
    )
    (comp (ref "U102")
      (value "MCP6002_")
      (footprint "eagle-import:SO08")
      (libsource (lib "eagle-import") (part "MCP6002_"))
    )
    (comp (ref "USB")
      (value "USB_HRS_ZX62-B-5PA(11)MICRO.B")
      (footprint "eagle-import:HRS_ZX62RD-AB-5P8")
      (libsource (lib "eagle-import") (part "USB_HRS_ZX62-B-5PA(11)MICRO.B"))
    )
    (comp (ref "Y2")
      (value "12MHZ")
      (footprint "eagle-import:CRYSTAL_2.5X2")
      (libsource (lib "eagle-import") (part "CRYSTAL2.5X2.0"))
    )
  )
  (nets
    (net (code "1") (name "+*-_B") (class "Default")
      (node (ref "JP4") (pin "1") (pinfunction "1_1") (pintype "passive"))
      (node (ref "U1") (pin "15") (pinfunction "GPIO12_15") (pintype "bidirectional"))
    )
    (net (code "2") (name "+*-_T") (class "Default")
      (node (ref "+*-") (pin "1") (pinfunction "1_1") (pintype "passive"))
      (node (ref "+*-") (pin "3") (pinfunction "3_3") (pintype "passive"))
      (node (ref "JP102") (pin "1") (pinfunction "1_1") (pintype "passive"))
    )
    (net (code "3") (name "+3V3") (class "Default")
      (node (ref "+*-") (pin "VDD") (pinfunction "VDD_VDD") (pintype "bidirectional"))
      (node (ref "ALT") (pin "VDD") (pinfunction "VDD_VDD") (pintype "bidirectional"))
      (node (ref "C101") (pin "1") (pinfunction "1_1") (pintype "passive"))
      (node (ref "C103") (pin "1") (pinfunction "1_1") (pintype "passive"))
      (node (ref "C105") (pin "1") (pinfunction "1_1") (pintype "passive"))
      (node (ref "C107") (pin "1") (pinfunction "1_1") (pintype "passive"))
      (node (ref "C111") (pin "+") (pinfunction "+_+") (pintype "passive"))
      (node (ref "C112") (pin "1") (pinfunction "1_1") (pintype "passive"))
      (node (ref "C113") (pin "1") (pinfunction "1_1") (pintype "passive"))
      (node (ref "C114") (pin "1") (pinfunction "1_1") (pintype "passive"))
      (node (ref "C117") (pin "1") (pinfunction "1_1") (pintype "passive"))
      (node (ref "C118") (pin "1") (pinfunction "1_1") (pintype "passive"))
      (node (ref "C119") (pin "1") (pinfunction "1_1") (pintype "passive"))
      (node (ref "C120") (pin "1") (pinfunction "1_1") (pintype "passive"))
      (node (ref "C121") (pin "1") (pinfunction "1_1") (pintype "passive"))
      (node (ref "C122") (pin "1") (pinfunction "1_1") (pintype "passive"))
      (node (ref "CHANCE") (pin "VDD") (pinfunction "VDD_VDD") (pintype "bidirectional"))
      (node (ref "CV") (pin "VDD") (pinfunction "VDD_VDD") (pintype "bidirectional"))
      (node (ref "IC100") (pin "2") (pinfunction "VOUT_2") (pintype "output"))
      (node (ref "IC101") (pin "18") (pinfunction "~{RESET}_18") (pintype "input"))
      (node (ref "IC101") (pin "9") (pinfunction "VDD_9") (pintype "power_in"))
      (node (ref "MUTE") (pin "VDD") (pinfunction "VDD_VDD") (pintype "bidirectional"))
      (node (ref "PRESET") (pin "VDD") (pinfunction "VDD_VDD") (pintype "bidirectional"))
      (node (ref "R108") (pin "2") (pinfunction "2_2") (pintype "passive"))
      (node (ref "R110") (pin "2") (pinfunction "2_2") (pintype "passive"))
      (node (ref "R112") (pin "1") (pinfunction "1_1") (pintype "passive"))
      (node (ref "R119") (pin "1") (pinfunction "1_1") (pintype "passive"))
      (node (ref "R124") (pin "1") (pinfunction "1_1") (pintype "passive"))
      (node (ref "R125") (pin "1") (pinfunction "1_1") (pintype "passive"))
      (node (ref "R128") (pin "1") (pinfunction "1_1") (pintype "passive"))
      (node (ref "R131") (pin "1") (pinfunction "1_1") (pintype "passive"))
      (node (ref "R136") (pin "1") (pinfunction "1_1") (pintype "passive"))
      (node (ref "R145") (pin "1") (pinfunction "1_1") (pintype "passive"))
      (node (ref "R149") (pin "1") (pinfunction "1_1") (pintype "passive"))
      (node (ref "TEMPO") (pin "VDD") (pinfunction "VDD_VDD") (pintype "bidirectional"))
      (node (ref "U$100") (pin "8") (pinfunction "VDD_8") (pintype "power_in"))
      (node (ref "U100") (pin "8") (pinfunction "V+_8") (pintype "power_in"))
      (node (ref "U101") (pin "8") (pinfunction "V+_8") (pintype "power_in"))
      (node (ref "U102") (pin "8") (pinfunction "V+_8") (pintype "power_in"))
    )
    (net (code "4") (name "+12V") (class "Default")
      (node (ref "C1") (pin "+") (pinfunction "+_+") (pintype "passive"))
      (node (ref "C109") (pin "+") (pinfunction "+_+") (pintype "passive"))
      (node (ref "C110") (pin "1") (pinfunction "1_1") (pintype "passive"))
      (node (ref "C6") (pin "+") (pinfunction "+_+") (pintype "passive"))
      (node (ref "C8") (pin "1") (pinfunction "1_1") (pintype "passive"))
      (node (ref "D2") (pin "C") (pinfunction "C_C") (pintype "passive"))
      (node (ref "IC100") (pin "3") (pinfunction "VIN_3") (pintype "input"))
      (node (ref "JP101") (pin "5") (pinfunction "5_5") (pintype "passive"))
      (node (ref "JP3") (pin "5") (pinfunction "5_5") (pintype "passive"))
      (node (ref "L1") (pin "1") (pinfunction "1_1") (pintype "passive"))
      (node (ref "R106") (pin "1") (pinfunction "1_1") (pintype "passive"))
      (node (ref "R113") (pin "1") (pinfunction "1_1") (pintype "passive"))
      (node (ref "R118") (pin "1") (pinfunction "1_1") (pintype "passive"))
      (node (ref "R133") (pin "1") (pinfunction "1_1") (pintype "passive"))
      (node (ref "R137") (pin "1") (pinfunction "1_1") (pintype "passive"))
    )
    (net (code "5") (name "-12V") (class "Default")
      (node (ref "C4") (pin "2") (pinfunction "2_2") (pintype "passive"))
      (node (ref "C5") (pin "-") (pinfunction "-_-") (pintype "passive"))
      (node (ref "D1") (pin "A") (pinfunction "A_A") (pintype "passive"))
    )
    (net (code "6") (name "3.3A") (class "Default")
      (node (ref "C13") (pin "+") (pinfunction "+_+") (pintype "passive"))
      (node (ref "C14") (pin "1") (pinfunction "1_1") (pintype "passive"))
      (node (ref "C15") (pin "1") (pinfunction "1_1") (pintype "passive"))
      (node (ref "C18") (pin "2") (pinfunction "2_2") (pintype "passive"))
      (node (ref "C20") (pin "1") (pinfunction "1_1") (pintype "passive"))
      (node (ref "C21") (pin "1") (pinfunction "1_1") (pintype "passive"))
      (node (ref "C22") (pin "2") (pinfunction "2_2") (pintype "passive"))
      (node (ref "C23") (pin "2") (pinfunction "2_2") (pintype "passive"))
      (node (ref "C24") (pin "2") (pinfunction "2_2") (pintype "passive"))
      (node (ref "C25") (pin "2") (pinfunction "2_2") (pintype "passive"))
      (node (ref "C26") (pin "2") (pinfunction "2_2") (pintype "passive"))
      (node (ref "J1") (pin "1") (pinfunction "1_1") (pintype "passive"))
      (node (ref "L4") (pin "2") (pinfunction "2_2") (pintype "passive"))
      (node (ref "R4") (pin "1") (pinfunction "1_1") (pintype "passive"))
      (node (ref "R5") (pin "2") (pinfunction "2_2") (pintype "passive"))
      (node (ref "U$2") (pin "8") (pinfunction "VCC_8") (pintype "bidirectional"))
      (node (ref "U1") (pin "1") (pinfunction "VDDIO_1") (pintype "bidirectional"))
      (node (ref "U1") (pin "10") (pinfunction "VDDIO_10") (pintype "bidirectional"))
      (node (ref "U1") (pin "22") (pinfunction "VDDIO_22") (pintype "bidirectional"))
      (node (ref "U1") (pin "33") (pinfunction "VDDIO_33") (pintype "bidirectional"))
      (node (ref "U1") (pin "42") (pinfunction "VDDIO_42") (pintype "bidirectional"))
      (node (ref "U1") (pin "43") (pinfunction "ADC_VDD_43") (pintype "bidirectional"))
      (node (ref "U1") (pin "44") (pinfunction "LDO_IN_44") (pintype "bidirectional"))
      (node (ref "U1") (pin "48") (pinfunction "USB_VDD_48") (pintype "bidirectional"))
      (node (ref "U1") (pin "49") (pinfunction "VDDIO_49") (pintype "bidirectional"))
    )
    (net (code "7") (name "ALT_B") (class "Default")
      (node (ref "JP2") (pin "12") (pinfunction "12_12") (pintype "passive"))
      (node (ref "U1") (pin "14") (pinfunction "GPIO11_14") (pintype "bidirectional"))
    )
    (net (code "8") (name "ALT_T") (class "Default")
      (node (ref "ALT") (pin "1") (pinfunction "1_1") (pintype "passive"))
      (node (ref "ALT") (pin "3") (pinfunction "3_3") (pintype "passive"))
      (node (ref "JP100") (pin "12") (pinfunction "12_12") (pintype "passive"))
    )
    (net (code "9") (name "A_B") (class "Default")
      (node (ref "JP2") (pin "2") (pinfunction "2_2") (pintype "passive"))
      (node (ref "U1") (pin "3") (pinfunction "GPIO1_3") (pintype "bidirectional"))
    )
    (net (code "10") (name "A_CV") (class "Default")
      (node (ref "C102") (pin "2") (pinfunction "2_2") (pintype "passive"))
      (node (ref "R115") (pin "1") (pinfunction "1_1") (pintype "passive"))
      (node (ref "U$100") (pin "4") (pinfunction "A0_4") (pintype "input"))
      (node (ref "U101") (pin "1") (pinfunction "OUT_1") (pintype "output"))
    )
    (net (code "11") (name "A_OUT_B") (class "Default")
      (node (ref "JP3") (pin "3") (pinfunction "3_3") (pintype "passive"))
      (node (ref "U1") (pin "40") (pinfunction "GPIO28/ADC2_40") (pintype "bidirectional"))
    )
    (net (code "12") (name "A_OUT_T") (class "Default")
      (node (ref "JP101") (pin "3") (pinfunction "3_3") (pintype "passive"))
      (node (ref "LED_A_OUT") (pin "K") (pinfunction "C_K") (pintype "passive"))
      (node (ref "R111") (pin "2") (pinfunction "2_2") (pintype "passive"))
    )
    (net (code "13") (name "A_T") (class "Default")
      (node (ref "A") (pin "3") (pinfunction "3_3") (pintype "passive"))
      (node (ref "A") (pin "4") (pinfunction "4_4") (pintype "passive"))
      (node (ref "JP100") (pin "2") (pinfunction "2_2") (pintype "passive"))
    )
    (net (code "14") (name "B_B") (class "Default")
      (node (ref "JP2") (pin "4") (pinfunction "4_4") (pintype "passive"))
      (node (ref "U1") (pin "5") (pinfunction "GPIO3_5") (pintype "bidirectional"))
    )
    (net (code "15") (name "B_CV") (class "Default")
      (node (ref "C104") (pin "2") (pinfunction "2_2") (pintype "passive"))
      (node (ref "R121") (pin "1") (pinfunction "1_1") (pintype "passive"))
      (node (ref "U$100") (pin "5") (pinfunction "A1_5") (pintype "input"))
      (node (ref "U101") (pin "7") (pinfunction "OUT_7") (pintype "output"))
    )
    (net (code "16") (name "B_OUT_B") (class "Default")
      (node (ref "JP3") (pin "4") (pinfunction "4_4") (pintype "passive"))
      (node (ref "U1") (pin "39") (pinfunction "GPIO27/ADC1_39") (pintype "bidirectional"))
    )
    (net (code "17") (name "B_OUT_T") (class "Default")
      (node (ref "JP101") (pin "4") (pinfunction "4_4") (pintype "passive"))
      (node (ref "LED_B_OUT") (pin "K") (pinfunction "C_K") (pintype "passive"))
      (node (ref "R120") (pin "2") (pinfunction "2_2") (pintype "passive"))
    )
    (net (code "18") (name "B_T") (class "Default")
      (node (ref "B") (pin "3") (pinfunction "3_3") (pintype "passive"))
      (node (ref "B") (pin "4") (pinfunction "4_4") (pintype "passive"))
      (node (ref "JP100") (pin "4") (pinfunction "4_4") (pintype "passive"))
    )
    (net (code "19") (name "CHAN_B") (class "Default")
      (node (ref "JP4") (pin "10") (pinfunction "10_10") (pintype "passive"))
      (node (ref "U1") (pin "34") (pinfunction "GPIO22_34") (pintype "bidirectional"))
    )
    (net (code "20") (name "CHAN_T") (class "Default")
      (node (ref "CHANCE") (pin "1") (pinfunction "1_1") (pintype "passive"))
      (node (ref "CHANCE") (pin "3") (pinfunction "3_3") (pintype "passive"))
      (node (ref "JP102") (pin "10") (pinfunction "10_10") (pintype "passive"))
    )
    (net (code "21") (name "CV_B") (class "Default")
      (node (ref "JP4") (pin "2") (pinfunction "2_2") (pintype "passive"))
      (node (ref "U1") (pin "16") (pinfunction "GPIO13_16") (pintype "bidirectional"))
    )
    (net (code "22") (name "CV_T") (class "Default")
      (node (ref "CV") (pin "1") (pinfunction "1_1") (pintype "passive"))
      (node (ref "CV") (pin "3") (pinfunction "3_3") (pintype "passive"))
      (node (ref "JP102") (pin "2") (pinfunction "2_2") (pintype "passive"))
    )
    (net (code "23") (name "C_B") (class "Default")
      (node (ref "JP2") (pin "8") (pinfunction "8_8") (pintype "passive"))
      (node (ref "U1") (pin "9") (pinfunction "GPIO7_9") (pintype "bidirectional"))
    )
    (net (code "24") (name "C_CV") (class "Default")
      (node (ref "C106") (pin "2") (pinfunction "2_2") (pintype "passive"))
      (node (ref "R132") (pin "1") (pinfunction "1_1") (pintype "passive"))
      (node (ref "U$100") (pin "6") (pinfunction "A2_6") (pintype "input"))
      (node (ref "U102") (pin "1") (pinfunction "OUT_1") (pintype "output"))
    )
    (net (code "25") (name "C_OUT_B") (class "Default")
      (node (ref "JP3") (pin "6") (pinfunction "6_6") (pintype "passive"))
      (node (ref "U1") (pin "38") (pinfunction "GPIO26/ADC0_38") (pintype "bidirectional"))
    )
    (net (code "26") (name "C_OUT_T") (class "Default")
      (node (ref "JP101") (pin "6") (pinfunction "6_6") (pintype "passive"))
      (node (ref "LED_C_OUT") (pin "K") (pinfunction "C_K") (pintype "passive"))
      (node (ref "R130") (pin "2") (pinfunction "2_2") (pintype "passive"))
    )
    (net (code "27") (name "C_T") (class "Default")
      (node (ref "C") (pin "3") (pinfunction "3_3") (pintype "passive"))
      (node (ref "C") (pin "4") (pinfunction "4_4") (pintype "passive"))
      (node (ref "JP100") (pin "8") (pinfunction "8_8") (pintype "passive"))
    )
    (net (code "28") (name "D_B") (class "Default")
      (node (ref "JP2") (pin "6") (pinfunction "6_6") (pintype "passive"))
      (node (ref "U1") (pin "7") (pinfunction "GPIO5_7") (pintype "bidirectional"))
    )
    (net (code "29") (name "D_CV") (class "Default")
      (node (ref "C108") (pin "2") (pinfunction "2_2") (pintype "passive"))
      (node (ref "R140") (pin "1") (pinfunction "1_1") (pintype "passive"))
      (node (ref "U$100") (pin "7") (pinfunction "A3_7") (pintype "input"))
      (node (ref "U102") (pin "7") (pinfunction "OUT_7") (pintype "output"))
    )
    (net (code "30") (name "D_OUT_B") (class "Default")
      (node (ref "JP3") (pin "7") (pinfunction "7_7") (pintype "passive"))
      (node (ref "U1") (pin "37") (pinfunction "GPIO25_37") (pintype "bidirectional"))
    )
    (net (code "31") (name "D_OUT_T") (class "Default")
      (node (ref "JP101") (pin "7") (pinfunction "7_7") (pintype "passive"))
      (node (ref "LED_D_OUT") (pin "K") (pinfunction "C_K") (pintype "passive"))
      (node (ref "R138") (pin "2") (pinfunction "2_2") (pintype "passive"))
    )
    (net (code "32") (name "D_T") (class "Default")
      (node (ref "D") (pin "3") (pinfunction "3_3") (pintype "passive"))
      (node (ref "D") (pin "4") (pinfunction "4_4") (pintype "passive"))
      (node (ref "JP100") (pin "6") (pinfunction "6_6") (pintype "passive"))
    )
    (net (code "33") (name "ENC_A_B") (class "Default")
      (node (ref "JP4") (pin "5") (pinfunction "5_5") (pintype "passive"))
      (node (ref "U1") (pin "29") (pinfunction "GPIO18_29") (pintype "bidirectional"))
    )
    (net (code "34") (name "ENC_A_T") (class "Default")
      (node (ref "C116") (pin "1") (pinfunction "1_1") (pintype "passive"))
      (node (ref "JP102") (pin "5") (pinfunction "5_5") (pintype "passive"))
      (node (ref "R150") (pin "1") (pinfunction "1_1") (pintype "passive"))
    )
    (net (code "35") (name "ENC_B_B") (class "Default")
      (node (ref "JP4") (pin "6") (pinfunction "6_6") (pintype "passive"))
      (node (ref "U1") (pin "30") (pinfunction "GPIO19_30") (pintype "bidirectional"))
    )
    (net (code "36") (name "ENC_B_T") (class "Default")
      (node (ref "C115") (pin "2") (pinfunction "2_2") (pintype "passive"))
      (node (ref "JP102") (pin "6") (pinfunction "6_6") (pintype "passive"))
      (node (ref "R146") (pin "2") (pinfunction "2_2") (pintype "passive"))
    )
    (net (code "37") (name "ENC_SW_B") (class "Default")
      (node (ref "JP4") (pin "11") (pinfunction "11_11") (pintype "passive"))
      (node (ref "U1") (pin "35") (pinfunction "GPIO23_35") (pintype "bidirectional"))
    )
    (net (code "38") (name "ENC_SW_T") (class "Default")
      (node (ref "ENCODER") (pin "E") (pinfunction "E_E") (pintype "passive"))
      (node (ref "JP102") (pin "11") (pinfunction "11_11") (pintype "passive"))
    )
    (net (code "39") (name "GND") (class "Default")
      (node (ref "+*-") (pin "2") (pinfunction "2_2") (pintype "passive"))
      (node (ref "+*-") (pin "4") (pinfunction "4_4") (pintype "passive"))
      (node (ref "+*-") (pin "GND") (pinfunction "GND_GND") (pintype "bidirectional"))
      (node (ref "A") (pin "1") (pinfunction "1_1") (pintype "passive"))
      (node (ref "A") (pin "2") (pinfunction "2_2") (pintype "passive"))
      (node (ref "ALT") (pin "2") (pinfunction "2_2") (pintype "passive"))
      (node (ref "ALT") (pin "4") (pinfunction "4_4") (pintype "passive"))
      (node (ref "ALT") (pin "GND") (pinfunction "GND_GND") (pintype "bidirectional"))
      (node (ref "A_CV") (pin "P1") (pinfunction "1_P1") (pintype "passive"))
      (node (ref "A_CV") (pin "P2") (pinfunction "2_P2") (pintype "passive"))
      (node (ref "A_OUT") (pin "P1") (pinfunction "1_P1") (pintype "passive"))
      (node (ref "B") (pin "1") (pinfunction "1_1") (pintype "passive"))
      (node (ref "B") (pin "2") (pinfunction "2_2") (pintype "passive"))
      (node (ref "B_CV") (pin "P1") (pinfunction "1_P1") (pintype "passive"))
      (node (ref "B_CV") (pin "P2") (pinfunction "2_P2") (pintype "passive"))
      (node (ref "B_OUT") (pin "P1") (pinfunction "1_P1") (pintype "passive"))
      (node (ref "C") (pin "1") (pinfunction "1_1") (pintype "passive"))
      (node (ref "C") (pin "2") (pinfunction "2_2") (pintype "passive"))
      (node (ref "C1") (pin "-") (pinfunction "-_-") (pintype "passive"))
      (node (ref "C101") (pin "2") (pinfunction "2_2") (pintype "passive"))
      (node (ref "C103") (pin "2") (pinfunction "2_2") (pintype "passive"))
      (node (ref "C105") (pin "2") (pinfunction "2_2") (pintype "passive"))
      (node (ref "C107") (pin "2") (pinfunction "2_2") (pintype "passive"))
      (node (ref "C109") (pin "-") (pinfunction "-_-") (pintype "passive"))
      (node (ref "C110") (pin "2") (pinfunction "2_2") (pintype "passive"))
      (node (ref "C111") (pin "-") (pinfunction "-_-") (pintype "passive"))
      (node (ref "C112") (pin "2") (pinfunction "2_2") (pintype "passive"))
      (node (ref "C113") (pin "2") (pinfunction "2_2") (pintype "passive"))
      (node (ref "C114") (pin "2") (pinfunction "2_2") (pintype "passive"))
      (node (ref "C115") (pin "1") (pinfunction "1_1") (pintype "passive"))
      (node (ref "C116") (pin "2") (pinfunction "2_2") (pintype "passive"))
      (node (ref "C117") (pin "2") (pinfunction "2_2") (pintype "passive"))
      (node (ref "C118") (pin "2") (pinfunction "2_2") (pintype "passive"))
      (node (ref "C119") (pin "2") (pinfunction "2_2") (pintype "passive"))
      (node (ref "C12") (pin "1") (pinfunction "1_1") (pintype "passive"))
      (node (ref "C120") (pin "2") (pinfunction "2_2") (pintype "passive"))
      (node (ref "C121") (pin "2") (pinfunction "2_2") (pintype "passive"))
      (node (ref "C122") (pin "2") (pinfunction "2_2") (pintype "passive"))
      (node (ref "C13") (pin "-") (pinfunction "-_-") (pintype "passive"))
      (node (ref "C14") (pin "2") (pinfunction "2_2") (pintype "passive"))
      (node (ref "C15") (pin "2") (pinfunction "2_2") (pintype "passive"))
      (node (ref "C16") (pin "2") (pinfunction "2_2") (pintype "passive"))
      (node (ref "C17") (pin "1") (pinfunction "1_1") (pintype "passive"))
      (node (ref "C18") (pin "1") (pinfunction "1_1") (pintype "passive"))
      (node (ref "C19") (pin "2") (pinfunction "2_2") (pintype "passive"))
      (node (ref "C2") (pin "2") (pinfunction "2_2") (pintype "passive"))
      (node (ref "C20") (pin "2") (pinfunction "2_2") (pintype "passive"))
      (node (ref "C21") (pin "2") (pinfunction "2_2") (pintype "passive"))
      (node (ref "C22") (pin "1") (pinfunction "1_1") (pintype "passive"))
      (node (ref "C23") (pin "1") (pinfunction "1_1") (pintype "passive"))
      (node (ref "C24") (pin "1") (pinfunction "1_1") (pintype "passive"))
      (node (ref "C25") (pin "1") (pinfunction "1_1") (pintype "passive"))
      (node (ref "C26") (pin "1") (pinfunction "1_1") (pintype "passive"))
      (node (ref "C27") (pin "1") (pinfunction "1_1") (pintype "passive"))
      (node (ref "C28") (pin "1") (pinfunction "1_1") (pintype "passive"))
      (node (ref "C29") (pin "2") (pinfunction "2_2") (pintype "passive"))
      (node (ref "C3") (pin "2") (pinfunction "2_2") (pintype "passive"))
      (node (ref "C4") (pin "1") (pinfunction "1_1") (pintype "passive"))
      (node (ref "C5") (pin "+") (pinfunction "+_+") (pintype "passive"))
      (node (ref "C6") (pin "-") (pinfunction "-_-") (pintype "passive"))
      (node (ref "C7") (pin "2") (pinfunction "2_2") (pintype "passive"))
      (node (ref "C8") (pin "2") (pinfunction "2_2") (pintype "passive"))
      (node (ref "C9") (pin "2") (pinfunction "2_2") (pintype "passive"))
      (node (ref "CHANCE") (pin "2") (pinfunction "2_2") (pintype "passive"))
      (node (ref "CHANCE") (pin "4") (pinfunction "4_4") (pintype "passive"))
      (node (ref "CHANCE") (pin "GND") (pinfunction "GND_GND") (pintype "bidirectional"))
      (node (ref "CV") (pin "2") (pinfunction "2_2") (pintype "passive"))
      (node (ref "CV") (pin "4") (pinfunction "4_4") (pintype "passive"))
      (node (ref "CV") (pin "GND") (pinfunction "GND_GND") (pintype "bidirectional"))
      (node (ref "C_CV") (pin "P1") (pinfunction "1_P1") (pintype "passive"))
      (node (ref "C_CV") (pin "P2") (pinfunction "2_P2") (pintype "passive"))
      (node (ref "C_OUT") (pin "P1") (pinfunction "1_P1") (pintype "passive"))
      (node (ref "D") (pin "1") (pinfunction "1_1") (pintype "passive"))
      (node (ref "D") (pin "2") (pinfunction "2_2") (pintype "passive"))
      (node (ref "D3") (pin "A") (pinfunction "A_A") (pintype "passive"))
      (node (ref "D_CV") (pin "P1") (pinfunction "1_P1") (pintype "passive"))
      (node (ref "D_CV") (pin "P2") (pinfunction "2_P2") (pintype "passive"))
      (node (ref "D_OUT") (pin "P1") (pinfunction "1_P1") (pintype "passive"))
      (node (ref "ENCODER") (pin "B") (pinfunction "C_B") (pintype "passive"))
      (node (ref "ENCODER") (pin "D") (pinfunction "D_D") (pintype "passive"))
      (node (ref "IC100") (pin "1") (pinfunction "GND_1") (pintype "power_in"))
      (node (ref "IC101") (pin "10") (pinfunction "VSS_10") (pintype "power_in"))
      (node (ref "IC101") (pin "15") (pinfunction "A0_15") (pintype "input"))
      (node (ref "IC101") (pin "16") (pinfunction "A1_16") (pintype "input"))
      (node (ref "IC101") (pin "17") (pinfunction "A2_17") (pintype "input"))
      (node (ref "J1") (pin "3") (pinfunction "3_3") (pintype "passive"))
      (node (ref "J1") (pin "5") (pinfunction "5_5") (pintype "passive"))
      (node (ref "J1") (pin "9") (pinfunction "9_9") (pintype "passive"))
      (node (ref "JP1") (pin "1") (pinfunction "1_1") (pintype "passive"))
      (node (ref "JP100") (pin "13") (pinfunction "13_13") (pintype "passive"))
      (node (ref "JP100") (pin "14") (pinfunction "14_14") (pintype "passive"))
      (node (ref "JP100") (pin "15") (pinfunction "15_15") (pintype "passive"))
      (node (ref "JP101") (pin "8") (pinfunction "8_8") (pintype "passive"))
      (node (ref "JP2") (pin "13") (pinfunction "13_13") (pintype "passive"))
      (node (ref "JP2") (pin "14") (pinfunction "14_14") (pintype "passive"))
      (node (ref "JP2") (pin "15") (pinfunction "15_15") (pintype "passive"))
      (node (ref "JP3") (pin "8") (pinfunction "8_8") (pintype "passive"))
      (node (ref "MUTE") (pin "2") (pinfunction "2_2") (pintype "passive"))
      (node (ref "MUTE") (pin "4") (pinfunction "4_4") (pintype "passive"))
      (node (ref "MUTE") (pin "GND") (pinfunction "GND_GND") (pintype "bidirectional"))
      (node (ref "PLAY") (pin "1") (pinfunction "1_1") (pintype "passive"))
      (node (ref "PLAY") (pin "2") (pinfunction "2_2") (pintype "passive"))
      (node (ref "POWER") (pin "3") (pinfunction "3_3") (pintype "passive"))
      (node (ref "POWER") (pin "4") (pinfunction "4_4") (pintype "passive"))
      (node (ref "POWER") (pin "5") (pinfunction "5_5") (pintype "passive"))
      (node (ref "POWER") (pin "6") (pinfunction "6_6") (pintype "passive"))
      (node (ref "POWER") (pin "7") (pinfunction "7_7") (pintype "passive"))
      (node (ref "POWER") (pin "8") (pinfunction "8_8") (pintype "passive"))
      (node (ref "PRESE") (pin "P1") (pinfunction "1_P1") (pintype "passive"))
      (node (ref "PRESE") (pin "P2") (pinfunction "2_P2") (pintype "passive"))
      (node (ref "PRESET") (pin "2") (pinfunction "2_2") (pintype "passive"))
      (node (ref "PRESET") (pin "4") (pinfunction "4_4") (pintype "passive"))
      (node (ref "PRESET") (pin "GND") (pinfunction "GND_GND") (pintype "bidirectional"))
      (node (ref "Q100") (pin "2") (pinfunction "E_2") (pintype "passive"))
      (node (ref "Q101") (pin "2") (pinfunction "E_2") (pintype "passive"))
      (node (ref "Q102") (pin "2") (pinfunction "E_2") (pintype "passive"))
      (node (ref "Q103") (pin "2") (pinfunction "E_2") (pintype "passive"))
      (node (ref "Q104") (pin "2") (pinfunction "E_2") (pintype "passive"))
      (node (ref "Q105") (pin "2") (pinfunction "E_2") (pintype "passive"))
      (node (ref "Q106") (pin "2") (pinfunction "E_2") (pintype "passive"))
      (node (ref "R100") (pin "1") (pinfunction "1_1") (pintype "passive"))
      (node (ref "R102") (pin "1") (pinfunction "1_1") (pintype "passive"))
      (node (ref "R117") (pin "2") (pinfunction "2_2") (pintype "passive"))
      (node (ref "R126") (pin "2") (pinfunction "2_2") (pintype "passive"))
      (node (ref "R127") (pin "2") (pinfunction "2_2") (pintype "passive"))
      (node (ref "R135") (pin "2") (pinfunction "2_2") (pintype "passive"))
      (node (ref "R142") (pin "2") (pinfunction "2_2") (pintype "passive"))
      (node (ref "R143") (pin "1") (pinfunction "1_1") (pintype "passive"))
      (node (ref "R144") (pin "1") (pinfunction "1_1") (pintype "passive"))
      (node (ref "R148") (pin "2") (pinfunction "2_2") (pintype "passive"))
      (node (ref "R2") (pin "1") (pinfunction "1_1") (pintype "passive"))
      (node (ref "R7") (pin "1") (pinfunction "1_1") (pintype "passive"))
      (node (ref "RESE") (pin "P1") (pinfunction "1_P1") (pintype "passive"))
      (node (ref "ST/SP") (pin "P1") (pinfunction "1_P1") (pintype "passive"))
      (node (ref "SW5") (pin "3") (pinfunction "P_3") (pintype "passive"))
      (node (ref "SW5") (pin "4") (pinfunction "P1_4") (pintype "passive"))
      (node (ref "SYNC") (pin "P1") (pinfunction "1_P1") (pintype "passive"))
      (node (ref "TEMPO") (pin "2") (pinfunction "2_2") (pintype "passive"))
      (node (ref "TEMPO") (pin "4") (pinfunction "4_4") (pintype "passive"))
      (node (ref "TEMPO") (pin "GND") (pinfunction "GND_GND") (pintype "bidirectional"))
      (node (ref "U$1") (pin "2") (pinfunction "GND_2") (pintype "bidirectional"))
      (node (ref "U$100") (pin "3") (pinfunction "GND_3") (pintype "power_in"))
      (node (ref "U$2") (pin "4") (pinfunction "GND_4") (pintype "bidirectional"))
      (node (ref "U1") (pin "19") (pinfunction "TESTEN_19") (pintype "bidirectional"))
      (node (ref "U1") (pin "EPAD") (pinfunction "GND_EPAD") (pintype "bidirectional"))
      (node (ref "U100") (pin "3") (pinfunction "+IN_3") (pintype "input"))
      (node (ref "U100") (pin "4") (pinfunction "V-_4") (pintype "power_in"))
      (node (ref "U100") (pin "5") (pinfunction "+IN_5") (pintype "input"))
      (node (ref "U101") (pin "3") (pinfunction "+IN_3") (pintype "input"))
      (node (ref "U101") (pin "4") (pinfunction "V-_4") (pintype "power_in"))
      (node (ref "U101") (pin "5") (pinfunction "+IN_5") (pintype "input"))
      (node (ref "U102") (pin "3") (pinfunction "+IN_3") (pintype "input"))
      (node (ref "U102") (pin "4") (pinfunction "V-_4") (pintype "power_in"))
      (node (ref "U102") (pin "5") (pinfunction "+IN_5") (pintype "input"))
      (node (ref "USB") (pin "5") (pinfunction "GND_5") (pintype "bidirectional"))
    )
    (net (code "40") (name "I2C0_SCL_B") (class "Default")
      (node (ref "JP3") (pin "2") (pinfunction "2_2") (pintype "passive"))
      (node (ref "U1") (pin "28") (pinfunction "GPIO17_28") (pintype "bidirectional"))
    )
    (net (code "41") (name "I2C0_SCL_T") (class "Default")
      (node (ref "IC101") (pin "12") (pinfunction "SCL_12") (pintype "input"))
      (node (ref "JP101") (pin "2") (pinfunction "2_2") (pintype "passive"))
      (node (ref "R128") (pin "2") (pinfunction "2_2") (pintype "passive"))
      (node (ref "U$100") (pin "10") (pinfunction "SCL_10") (pintype "bidirectional"))
    )
    (net (code "42") (name "I2C0_SDA_B") (class "Default")
      (node (ref "JP3") (pin "1") (pinfunction "1_1") (pintype "passive"))
      (node (ref "U1") (pin "27") (pinfunction "GPIO16_27") (pintype "bidirectional"))
    )
    (net (code "43") (name "I2C0_SDA_T") (class "Default")
      (node (ref "IC101") (pin "13") (pinfunction "SDA_13") (pintype "bidirectional"))
      (node (ref "JP101") (pin "1") (pinfunction "1_1") (pintype "passive"))
      (node (ref "R124") (pin "2") (pinfunction "2_2") (pintype "passive"))
      (node (ref "U$100") (pin "9") (pinfunction "SDA_9") (pintype "bidirectional"))
    )
    (net (code "44") (name "LA_B") (class "Default")
      (node (ref "JP2") (pin "1") (pinfunction "1_1") (pintype "passive"))
      (node (ref "U1") (pin "2") (pinfunction "GPIO0_2") (pintype "bidirectional"))
    )
    (net (code "45") (name "LA_T") (class "Default")
      (node (ref "A") (pin "P$1") (pinfunction "P$1_P$1") (pintype "bidirectional"))
      (node (ref "JP100") (pin "1") (pinfunction "1_1") (pintype "passive"))
    )
    (net (code "46") (name "LB_B") (class "Default")
      (node (ref "JP2") (pin "3") (pinfunction "3_3") (pintype "passive"))
      (node (ref "U1") (pin "4") (pinfunction "GPIO2_4") (pintype "bidirectional"))
    )
    (net (code "47") (name "LB_T") (class "Default")
      (node (ref "B") (pin "P$1") (pinfunction "P$1_P$1") (pintype "bidirectional"))
      (node (ref "JP100") (pin "3") (pinfunction "3_3") (pintype "passive"))
    )
    (net (code "48") (name "LC_B") (class "Default")
      (node (ref "JP2") (pin "5") (pinfunction "5_5") (pintype "passive"))
      (node (ref "U1") (pin "6") (pinfunction "GPIO4_6") (pintype "bidirectional"))
    )
    (net (code "49") (name "LC_T") (class "Default")
      (node (ref "C") (pin "P$1") (pinfunction "P$1_P$1") (pintype "bidirectional"))
      (node (ref "JP100") (pin "5") (pinfunction "5_5") (pintype "passive"))
    )
    (net (code "50") (name "LD_B") (class "Default")
      (node (ref "JP2") (pin "7") (pinfunction "7_7") (pintype "passive"))
      (node (ref "U1") (pin "8") (pinfunction "GPIO6_8") (pintype "bidirectional"))
    )
    (net (code "51") (name "LD_T") (class "Default")
      (node (ref "D") (pin "P$1") (pinfunction "P$1_P$1") (pintype "bidirectional"))
      (node (ref "JP100") (pin "7") (pinfunction "7_7") (pintype "passive"))
    )
    (net (code "52") (name "LPLAY") (class "Default")
      (node (ref "IC101") (pin "7") (pinfunction "GPB6_7") (pintype "bidirectional"))
      (node (ref "PLAY") (pin "P$1") (pinfunction "P$1_P$1") (pintype "bidirectional"))
    )
    (net (code "53") (name "MEM_CLK") (class "Default")
      (node (ref "U$2") (pin "6") (pinfunction "SCK_6") (pintype "bidirectional"))
      (node (ref "U1") (pin "52") (pinfunction "QSPI_SCLK_52") (pintype "bidirectional"))
    )
    (net (code "54") (name "MEM_CS") (class "Default")
      (node (ref "R5") (pin "1") (pinfunction "1_1") (pintype "passive"))
      (node (ref "R6") (pin "1") (pinfunction "1_1") (pintype "passive"))
      (node (ref "U$2") (pin "1") (pinfunction "CS_1") (pintype "bidirectional"))
      (node (ref "U1") (pin "56") (pinfunction "QSPI_~{CS}_56") (pintype "bidirectional"))
    )
    (net (code "55") (name "MEM_I00") (class "Default")
      (node (ref "U$2") (pin "5") (pinfunction "DI_5") (pintype "bidirectional"))
      (node (ref "U1") (pin "53") (pinfunction "QSPI_SD0_53") (pintype "bidirectional"))
    )
    (net (code "56") (name "MEM_I01") (class "Default")
      (node (ref "U$2") (pin "2") (pinfunction "D0_2") (pintype "bidirectional"))
      (node (ref "U1") (pin "55") (pinfunction "QSPI_SD1_55") (pintype "bidirectional"))
    )
    (net (code "57") (name "MEM_I02") (class "Default")
      (node (ref "U$2") (pin "3") (pinfunction "I02_3") (pintype "bidirectional"))
      (node (ref "U1") (pin "54") (pinfunction "QSPI_SD2_54") (pintype "bidirectional"))
    )
    (net (code "58") (name "MEM_I03") (class "Default")
      (node (ref "U$2") (pin "7") (pinfunction "I03_7") (pintype "bidirectional"))
      (node (ref "U1") (pin "51") (pinfunction "QSPI_SD3_51") (pintype "bidirectional"))
    )
    (net (code "59") (name "MUTE_B") (class "Default")
      (node (ref "JP4") (pin "3") (pinfunction "3_3") (pintype "passive"))
      (node (ref "U1") (pin "17") (pinfunction "GPIO14_17") (pintype "bidirectional"))
    )
    (net (code "60") (name "MUTE_T") (class "Default")
      (node (ref "JP102") (pin "3") (pinfunction "3_3") (pintype "passive"))
      (node (ref "MUTE") (pin "1") (pinfunction "1_1") (pintype "passive"))
      (node (ref "MUTE") (pin "3") (pinfunction "3_3") (pintype "passive"))
    )
    (net (code "61") (name "NEO_B") (class "Default")
      (node (ref "JP2") (pin "9") (pinfunction "9_9") (pintype "passive"))
      (node (ref "U1") (pin "11") (pinfunction "GPIO8_11") (pintype "bidirectional"))
    )
    (net (code "62") (name "NEO_T") (class "Default")
      (node (ref "JP100") (pin "9") (pinfunction "9_9") (pintype "passive"))
      (node (ref "R147") (pin "1") (pinfunction "1_1") (pintype "passive"))
    )
    (net (code "63") (name "Net-(+*--DI)") (class "Default")
      (node (ref "+*-") (pin "DIN") (pinfunction "DI_DIN") (pintype "bidirectional"))
      (node (ref "MUTE") (pin "DOUT") (pinfunction "DO_DOUT") (pintype "bidirectional"))
    )
    (net (code "64") (name "Net-(A-PadP$2)") (class "Default")
      (node (ref "A") (pin "P$2") (pinfunction "P$2_P$2") (pintype "bidirectional"))
      (node (ref "R117") (pin "1") (pinfunction "1_1") (pintype "passive"))
    )
    (net (code "65") (name "Net-(ALT-DI)") (class "Default")
      (node (ref "ALT") (pin "DIN") (pinfunction "DI_DIN") (pintype "bidirectional"))
      (node (ref "R147") (pin "2") (pinfunction "2_2") (pintype "passive"))
    )
    (net (code "66") (name "Net-(ALT-DO)") (class "Default")
      (node (ref "ALT") (pin "DOUT") (pinfunction "DO_DOUT") (pintype "bidirectional"))
      (node (ref "CV") (pin "DIN") (pinfunction "DI_DIN") (pintype "bidirectional"))
    )
    (net (code "67") (name "Net-(A_CV-3)") (class "Default")
      (node (ref "A_CV") (pin "P3") (pinfunction "3_P3") (pintype "passive"))
      (node (ref "R114") (pin "2") (pinfunction "2_2") (pintype "passive"))
    )
    (net (code "68") (name "Net-(A_OUT-3)") (class "Default")
      (node (ref "A_OUT") (pin "P3") (pinfunction "3_P3") (pintype "passive"))
      (node (ref "R116") (pin "2") (pinfunction "2_2") (pintype "passive"))
    )
    (net (code "69") (name "Net-(B-PadP$2)") (class "Default")
      (node (ref "B") (pin "P$2") (pinfunction "P$2_P$2") (pintype "bidirectional"))
      (node (ref "R126") (pin "1") (pinfunction "1_1") (pintype "passive"))
    )
    (net (code "70") (name "Net-(BAR-C)") (class "Default")
      (node (ref "BAR") (pin "K") (pinfunction "C_K") (pintype "passive"))
      (node (ref "R143") (pin "2") (pinfunction "2_2") (pintype "passive"))
    )
    (net (code "71") (name "Net-(BEAT-C)") (class "Default")
      (node (ref "BEAT") (pin "K") (pinfunction "C_K") (pintype "passive"))
      (node (ref "R144") (pin "2") (pinfunction "2_2") (pintype "passive"))
    )
    (net (code "72") (name "Net-(B_CV-3)") (class "Default")
      (node (ref "B_CV") (pin "P3") (pinfunction "3_P3") (pintype "passive"))
      (node (ref "R123") (pin "2") (pinfunction "2_2") (pintype "passive"))
    )
    (net (code "73") (name "Net-(B_OUT-3)") (class "Default")
      (node (ref "B_OUT") (pin "P3") (pinfunction "3_P3") (pintype "passive"))
      (node (ref "R122") (pin "2") (pinfunction "2_2") (pintype "passive"))
    )
    (net (code "74") (name "Net-(C-PadP$2)") (class "Default")
      (node (ref "C") (pin "P$2") (pinfunction "P$2_P$2") (pintype "bidirectional"))
      (node (ref "R135") (pin "1") (pinfunction "1_1") (pintype "passive"))
    )
    (net (code "75") (name "Net-(C2-Pad1)") (class "Default")
      (node (ref "C2") (pin "1") (pinfunction "1_1") (pintype "passive"))
      (node (ref "L1") (pin "2") (pinfunction "2_2") (pintype "passive"))
      (node (ref "L2") (pin "1") (pinfunction "1_1") (pintype "passive"))
    )
    (net (code "76") (name "Net-(C11-Pad2)") (class "Default")
      (node (ref "C11") (pin "2") (pinfunction "2_2") (pintype "passive"))
      (node (ref "C12") (pin "2") (pinfunction "2_2") (pintype "passive"))
      (node (ref "L3") (pin "2") (pinfunction "2_2") (pintype "passive"))
      (node (ref "L4") (pin "1") (pinfunction "1_1") (pintype "passive"))
      (node (ref "R3") (pin "1") (pinfunction "1_1") (pintype "passive"))
    )
    (net (code "77") (name "Net-(C16-Pad1)") (class "Default")
      (node (ref "C16") (pin "1") (pinfunction "1_1") (pintype "passive"))
      (node (ref "R7") (pin "2") (pinfunction "2_2") (pintype "passive"))
      (node (ref "USB") (pin "G") (pinfunction "SHIELD_G") (pintype "bidirectional"))
      (node (ref "USB") (pin "G2") (pinfunction "SHIELD_G2") (pintype "bidirectional"))
      (node (ref "USB") (pin "G3") (pinfunction "SHIELD_G3") (pintype "bidirectional"))
      (node (ref "USB") (pin "G4") (pinfunction "SHIELD_G4") (pintype "bidirectional"))
    )
    (net (code "78") (name "Net-(C29-Pad1)") (class "Default")
      (node (ref "C29") (pin "1") (pinfunction "1_1") (pintype "passive"))
      (node (ref "R10") (pin "1") (pinfunction "1_1") (pintype "passive"))
      (node (ref "Y2") (pin "1") (pinfunction "1_1") (pintype "passive"))
    )
    (net (code "79") (name "Net-(CHANCE-DI)") (class "Default")
      (node (ref "CHANCE") (pin "DIN") (pinfunction "DI_DIN") (pintype "bidirectional"))
      (node (ref "TEMPO") (pin "DOUT") (pinfunction "DO_DOUT") (pintype "bidirectional"))
    )
    (net (code "80") (name "Net-(CHANCE-DO)") (class "Default")
      (node (ref "CHANCE") (pin "DOUT") (pinfunction "DO_DOUT") (pintype "bidirectional"))
      (node (ref "MUTE") (pin "DIN") (pinfunction "DI_DIN") (pintype "bidirectional"))
    )
    (net (code "81") (name "Net-(CV-DO)") (class "Default")
      (node (ref "CV") (pin "DOUT") (pinfunction "DO_DOUT") (pintype "bidirectional"))
      (node (ref "PRESET") (pin "DIN") (pinfunction "DI_DIN") (pintype "bidirectional"))
    )
    (net (code "82") (name "Net-(C_CV-3)") (class "Default")
      (node (ref "C_CV") (pin "P3") (pinfunction "3_P3") (pintype "passive"))
      (node (ref "R129") (pin "2") (pinfunction "2_2") (pintype "passive"))
    )
    (net (code "83") (name "Net-(C_OUT-3)") (class "Default")
      (node (ref "C_OUT") (pin "P3") (pinfunction "3_P3") (pintype "passive"))
      (node (ref "R134") (pin "2") (pinfunction "2_2") (pintype "passive"))
    )
    (net (code "84") (name "Net-(D-PadP$2)") (class "Default")
      (node (ref "D") (pin "P$2") (pinfunction "P$2_P$2") (pintype "bidirectional"))
      (node (ref "R142") (pin "1") (pinfunction "1_1") (pintype "passive"))
    )
    (net (code "85") (name "Net-(D1-PadC)") (class "Default")
      (node (ref "D1") (pin "C") (pinfunction "C_C") (pintype "passive"))
      (node (ref "F1") (pin "1") (pinfunction "1_1") (pintype "passive"))
    )
    (net (code "86") (name "Net-(D2-PadA)") (class "Default")
      (node (ref "D2") (pin "A") (pinfunction "A_A") (pintype "passive"))
      (node (ref "F2") (pin "1") (pinfunction "1_1") (pintype "passive"))
    )
    (net (code "87") (name "Net-(D_CV-3)") (class "Default")
      (node (ref "D_CV") (pin "P3") (pinfunction "3_P3") (pintype "passive"))
      (node (ref "R139") (pin "2") (pinfunction "2_2") (pintype "passive"))
    )
    (net (code "88") (name "Net-(D_OUT-3)") (class "Default")
      (node (ref "D_OUT") (pin "P3") (pinfunction "3_P3") (pintype "passive"))
      (node (ref "R141") (pin "2") (pinfunction "2_2") (pintype "passive"))
    )
    (net (code "89") (name "Net-(ENCODER-PadA)") (class "Default")
      (node (ref "ENCODER") (pin "A") (pinfunction "A_A") (pintype "passive"))
      (node (ref "R145") (pin "2") (pinfunction "2_2") (pintype "passive"))
      (node (ref "R146") (pin "1") (pinfunction "1_1") (pintype "passive"))
    )
    (net (code "90") (name "Net-(ENCODERA-B)") (class "Default")
      (node (ref "ENCODER") (pin "C") (pinfunction "B_C") (pintype "passive"))
      (node (ref "R149") (pin "2") (pinfunction "2_2") (pintype "passive"))
      (node (ref "R150") (pin "2") (pinfunction "2_2") (pintype "passive"))
    )
    (net (code "91") (name "Net-(F1-Pad2)") (class "Default")
      (node (ref "F1") (pin "2") (pinfunction "2_2") (pintype "passive"))
      (node (ref "POWER") (pin "1") (pinfunction "1_1") (pintype "passive"))
      (node (ref "POWER") (pin "2") (pinfunction "2_2") (pintype "passive"))
    )
    (net (code "92") (name "Net-(F2-Pad2)") (class "Default")
      (node (ref "F2") (pin "2") (pinfunction "2_2") (pintype "passive"))
      (node (ref "POWER") (pin "10") (pinfunction "10_10") (pintype "passive"))
      (node (ref "POWER") (pin "9") (pinfunction "9_9") (pintype "passive"))
    )
    (net (code "93") (name "Net-(IC101-GPA0)") (class "Default")
      (node (ref "IC101") (pin "21") (pinfunction "GPA0_21") (pintype "bidirectional"))
      (node (ref "LFD36BUE-101B") (pin "11") (pinfunction "A_11") (pintype "bidirectional"))
    )
    (net (code "94") (name "Net-(IC101-GPA1)") (class "Default")
      (node (ref "IC101") (pin "22") (pinfunction "GPA1_22") (pintype "bidirectional"))
      (node (ref "LFD36BUE-101B") (pin "7") (pinfunction "B_7") (pintype "bidirectional"))
    )
    (net (code "95") (name "Net-(IC101-GPA2)") (class "Default")
      (node (ref "IC101") (pin "23") (pinfunction "GPA2_23") (pintype "bidirectional"))
      (node (ref "LFD36BUE-101B") (pin "4") (pinfunction "C_4") (pintype "bidirectional"))
    )
    (net (code "96") (name "Net-(IC101-GPA3)") (class "Default")
      (node (ref "IC101") (pin "24") (pinfunction "GPA3_24") (pintype "bidirectional"))
      (node (ref "LFD36BUE-101B") (pin "2") (pinfunction "D_2") (pintype "bidirectional"))
    )
    (net (code "97") (name "Net-(IC101-GPA4)") (class "Default")
      (node (ref "IC101") (pin "25") (pinfunction "GPA4_25") (pintype "bidirectional"))
      (node (ref "LFD36BUE-101B") (pin "1") (pinfunction "E_1") (pintype "bidirectional"))
    )
    (net (code "98") (name "Net-(IC101-GPA5)") (class "Default")
      (node (ref "IC101") (pin "26") (pinfunction "GPA5_26") (pintype "bidirectional"))
      (node (ref "LFD36BUE-101B") (pin "10") (pinfunction "F_10") (pintype "bidirectional"))
    )
    (net (code "99") (name "Net-(IC101-GPA6)") (class "Default")
      (node (ref "IC101") (pin "27") (pinfunction "GPA6_27") (pintype "bidirectional"))
      (node (ref "LFD36BUE-101B") (pin "5") (pinfunction "G_5") (pintype "bidirectional"))
    )
    (net (code "100") (name "Net-(IC101-GPA7)") (class "Default")
      (node (ref "IC101") (pin "28") (pinfunction "GPA7_28") (pintype "bidirectional"))
      (node (ref "LFD36BUE-101B") (pin "3") (pinfunction "DP_3") (pintype "bidirectional"))
    )
    (net (code "101") (name "Net-(IC101-GPB0)") (class "Default")
      (node (ref "IC101") (pin "1") (pinfunction "GPB0_1") (pintype "bidirectional"))
      (node (ref "LFD36BUE-101B") (pin "12") (pinfunction "D1_12") (pintype "bidirectional"))
    )
    (net (code "102") (name "Net-(IC101-GPB1)") (class "Default")
      (node (ref "IC101") (pin "2") (pinfunction "GPB1_2") (pintype "bidirectional"))
      (node (ref "LFD36BUE-101B") (pin "9") (pinfunction "D2_9") (pintype "bidirectional"))
    )
    (net (code "103") (name "Net-(IC101-GPB2)") (class "Default")
      (node (ref "IC101") (pin "3") (pinfunction "GPB2_3") (pintype "bidirectional"))
      (node (ref "LFD36BUE-101B") (pin "8") (pinfunction "D3_8") (pintype "bidirectional"))
    )
    (net (code "104") (name "Net-(IC101-GPB3)") (class "Default")
      (node (ref "IC101") (pin "4") (pinfunction "GPB3_4") (pintype "bidirectional"))
      (node (ref "LFD36BUE-101B") (pin "6") (pinfunction "D4_6") (pintype "bidirectional"))
    )
    (net (code "105") (name "Net-(IC101-GPB4)") (class "Default")
      (node (ref "BAR") (pin "A") (pinfunction "A_A") (pintype "passive"))
      (node (ref "IC101") (pin "5") (pinfunction "GPB4_5") (pintype "bidirectional"))
    )
    (net (code "106") (name "Net-(IC101-GPB5)") (class "Default")
      (node (ref "BEAT") (pin "A") (pinfunction "A_A") (pintype "passive"))
      (node (ref "IC101") (pin "6") (pinfunction "GPB5_6") (pintype "bidirectional"))
    )
    (net (code "107") (name "Net-(LED_A_OUT-PadA)") (class "Default")
      (node (ref "LED_A_OUT") (pin "A") (pinfunction "A_A") (pintype "passive"))
      (node (ref "R112") (pin "2") (pinfunction "2_2") (pintype "passive"))
    )
    (net (code "108") (name "Net-(LED_B_OUT-PadA)") (class "Default")
      (node (ref "LED_B_OUT") (pin "A") (pinfunction "A_A") (pintype "passive"))
      (node (ref "R119") (pin "2") (pinfunction "2_2") (pintype "passive"))
    )
    (net (code "109") (name "Net-(LED_C_OUT-PadA)") (class "Default")
      (node (ref "LED_C_OUT") (pin "A") (pinfunction "A_A") (pintype "passive"))
      (node (ref "R131") (pin "2") (pinfunction "2_2") (pintype "passive"))
    )
    (net (code "110") (name "Net-(LED_D_OUT-PadA)") (class "Default")
      (node (ref "LED_D_OUT") (pin "A") (pinfunction "A_A") (pintype "passive"))
      (node (ref "R136") (pin "2") (pinfunction "2_2") (pintype "passive"))
    )
    (net (code "111") (name "Net-(PLAY-PadP$2)") (class "Default")
      (node (ref "PLAY") (pin "P$2") (pinfunction "P$2_P$2") (pintype "bidirectional"))
      (node (ref "R148") (pin "1") (pinfunction "1_1") (pintype "passive"))
    )
    (net (code "112") (name "Net-(PRESE-3)") (class "Default")
      (node (ref "PRESE") (pin "P3") (pinfunction "3_P3") (pintype "passive"))
      (node (ref "R104") (pin "2") (pinfunction "2_2") (pintype "passive"))
    )
    (net (code "113") (name "Net-(PRESET-DO)") (class "Default")
      (node (ref "PRESET") (pin "DOUT") (pinfunction "DO_DOUT") (pintype "bidirectional"))
      (node (ref "TEMPO") (pin "DIN") (pinfunction "DI_DIN") (pintype "bidirectional"))
    )
    (net (code "114") (name "Net-(Q100-B)") (class "Default")
      (node (ref "Q100") (pin "1") (pinfunction "B_1") (pintype "passive"))
      (node (ref "R109") (pin "1") (pinfunction "1_1") (pintype "passive"))
    )
    (net (code "115") (name "Net-(Q100-C)") (class "Default")
      (node (ref "Q100") (pin "3") (pinfunction "C_3") (pintype "passive"))
      (node (ref "R103") (pin "1") (pinfunction "1_1") (pintype "passive"))
      (node (ref "R106") (pin "2") (pinfunction "2_2") (pintype "passive"))
    )
    (net (code "116") (name "Net-(Q101-B)") (class "Default")
      (node (ref "Q101") (pin "1") (pinfunction "B_1") (pintype "passive"))
      (node (ref "R100") (pin "2") (pinfunction "2_2") (pintype "passive"))
      (node (ref "R101") (pin "1") (pinfunction "1_1") (pintype "passive"))
    )
    (net (code "117") (name "Net-(Q102-B)") (class "Default")
      (node (ref "Q102") (pin "1") (pinfunction "B_1") (pintype "passive"))
      (node (ref "R102") (pin "2") (pinfunction "2_2") (pintype "passive"))
      (node (ref "R105") (pin "1") (pinfunction "1_1") (pintype "passive"))
    )
    (net (code "118") (name "Net-(Q103-B)") (class "Default")
      (node (ref "Q103") (pin "1") (pinfunction "B_1") (pintype "passive"))
      (node (ref "R111") (pin "1") (pinfunction "1_1") (pintype "passive"))
    )
    (net (code "119") (name "Net-(Q103-C)") (class "Default")
      (node (ref "Q103") (pin "3") (pinfunction "C_3") (pintype "passive"))
      (node (ref "R113") (pin "2") (pinfunction "2_2") (pintype "passive"))
      (node (ref "R116") (pin "1") (pinfunction "1_1") (pintype "passive"))
    )
    (net (code "120") (name "Net-(Q104-B)") (class "Default")
      (node (ref "Q104") (pin "1") (pinfunction "B_1") (pintype "passive"))
      (node (ref "R120") (pin "1") (pinfunction "1_1") (pintype "passive"))
    )
    (net (code "121") (name "Net-(Q104-C)") (class "Default")
      (node (ref "Q104") (pin "3") (pinfunction "C_3") (pintype "passive"))
      (node (ref "R118") (pin "2") (pinfunction "2_2") (pintype "passive"))
      (node (ref "R122") (pin "1") (pinfunction "1_1") (pintype "passive"))
    )
    (net (code "122") (name "Net-(Q105-B)") (class "Default")
      (node (ref "Q105") (pin "1") (pinfunction "B_1") (pintype "passive"))
      (node (ref "R130") (pin "1") (pinfunction "1_1") (pintype "passive"))
    )
    (net (code "123") (name "Net-(Q105-C)") (class "Default")
      (node (ref "Q105") (pin "3") (pinfunction "C_3") (pintype "passive"))
      (node (ref "R133") (pin "2") (pinfunction "2_2") (pintype "passive"))
      (node (ref "R134") (pin "1") (pinfunction "1_1") (pintype "passive"))
    )
    (net (code "124") (name "Net-(Q106-B)") (class "Default")
      (node (ref "Q106") (pin "1") (pinfunction "B_1") (pintype "passive"))
      (node (ref "R138") (pin "1") (pinfunction "1_1") (pintype "passive"))
    )
    (net (code "125") (name "Net-(Q106-C)") (class "Default")
      (node (ref "Q106") (pin "3") (pinfunction "C_3") (pintype "passive"))
      (node (ref "R137") (pin "2") (pinfunction "2_2") (pintype "passive"))
      (node (ref "R141") (pin "1") (pinfunction "1_1") (pintype "passive"))
    )
    (net (code "126") (name "Net-(RESE-3)") (class "Default")
      (node (ref "R101") (pin "2") (pinfunction "2_2") (pintype "passive"))
      (node (ref "RESE") (pin "P3") (pinfunction "3_P3") (pintype "passive"))
    )
    (net (code "127") (name "Net-(ST/SP-3)") (class "Default")
      (node (ref "R103") (pin "2") (pinfunction "2_2") (pintype "passive"))
      (node (ref "ST/SP") (pin "P3") (pinfunction "3_P3") (pintype "passive"))
    )
    (net (code "128") (name "Net-(SW5-S)") (class "Default")
      (node (ref "R6") (pin "2") (pinfunction "2_2") (pintype "passive"))
      (node (ref "SW5") (pin "1") (pinfunction "S_1") (pintype "passive"))
      (node (ref "SW5") (pin "2") (pinfunction "S1_2") (pintype "passive"))
    )
    (net (code "129") (name "Net-(SYNC-3)") (class "Default")
      (node (ref "R105") (pin "2") (pinfunction "2_2") (pintype "passive"))
      (node (ref "SYNC") (pin "P3") (pinfunction "3_P3") (pintype "passive"))
    )
    (net (code "130") (name "Net-(U$1-BST)") (class "Default")
      (node (ref "C10") (pin "2") (pinfunction "2_2") (pintype "passive"))
      (node (ref "U$1") (pin "1") (pinfunction "BST_1") (pintype "bidirectional"))
    )
    (net (code "131") (name "Net-(U$1-EN)") (class "Default")
      (node (ref "R1") (pin "2") (pinfunction "2_2") (pintype "passive"))
      (node (ref "U$1") (pin "4") (pinfunction "EN_4") (pintype "power_in"))
    )
    (net (code "132") (name "Net-(U$1-FB)") (class "Default")
      (node (ref "C11") (pin "1") (pinfunction "1_1") (pintype "passive"))
      (node (ref "R2") (pin "2") (pinfunction "2_2") (pintype "passive"))
      (node (ref "R3") (pin "2") (pinfunction "2_2") (pintype "passive"))
      (node (ref "U$1") (pin "3") (pinfunction "FB_3") (pintype "bidirectional"))
    )
    (net (code "133") (name "Net-(U$1-SW)") (class "Default")
      (node (ref "C10") (pin "1") (pinfunction "1_1") (pintype "passive"))
      (node (ref "D3") (pin "C") (pinfunction "C_C") (pintype "passive"))
      (node (ref "L3") (pin "1") (pinfunction "1_1") (pintype "passive"))
      (node (ref "U$1") (pin "6") (pinfunction "SW_6") (pintype "power_in"))
    )
    (net (code "134") (name "Net-(U$1-VIN)") (class "Default")
      (node (ref "C3") (pin "1") (pinfunction "1_1") (pintype "passive"))
      (node (ref "C7") (pin "1") (pinfunction "1_1") (pintype "passive"))
      (node (ref "C9") (pin "1") (pinfunction "1_1") (pintype "passive"))
      (node (ref "L2") (pin "2") (pinfunction "2_2") (pintype "passive"))
      (node (ref "R1") (pin "1") (pinfunction "1_1") (pintype "passive"))
      (node (ref "U$1") (pin "5") (pinfunction "VIN_5") (pintype "bidirectional"))
    )
    (net (code "135") (name "Net-(U$100-ADDR)") (class "Default")
      (node (ref "R127") (pin "1") (pinfunction "1_1") (pintype "passive"))
      (node (ref "U$100") (pin "1") (pinfunction "ADDR_1") (pintype "bidirectional"))
    )
    (net (code "136") (name "Net-(U$100-ALRT)") (class "Default")
      (node (ref "R125") (pin "2") (pinfunction "2_2") (pintype "passive"))
      (node (ref "U$100") (pin "2") (pinfunction "ALRT_2") (pintype "bidirectional"))
    )
    (net (code "137") (name "Net-(U1-LDO_OUT)") (class "Default")
      (node (ref "C17") (pin "2") (pinfunction "2_2") (pintype "passive"))
      (node (ref "C19") (pin "1") (pinfunction "1_1") (pintype "passive"))
      (node (ref "C27") (pin "2") (pinfunction "2_2") (pintype "passive"))
      (node (ref "U1") (pin "23") (pinfunction "VDD_1V1_23") (pintype "bidirectional"))
      (node (ref "U1") (pin "45") (pinfunction "LDO_OUT_45") (pintype "bidirectional"))
      (node (ref "U1") (pin "50") (pinfunction "VDD_1V1_50") (pintype "bidirectional"))
    )
    (net (code "138") (name "Net-(U1-USB_D+)") (class "Default")
      (node (ref "R8") (pin "2") (pinfunction "2_2") (pintype "passive"))
      (node (ref "U1") (pin "47") (pinfunction "USB_D+_47") (pintype "bidirectional"))
    )
    (net (code "139") (name "Net-(U1-USB_D-)") (class "Default")
      (node (ref "R9") (pin "1") (pinfunction "1_1") (pintype "passive"))
      (node (ref "U1") (pin "46") (pinfunction "USB_D-_46") (pintype "bidirectional"))
    )
    (net (code "140") (name "Net-(U1-XIN)") (class "Default")
      (node (ref "C28") (pin "2") (pinfunction "2_2") (pintype "passive"))
      (node (ref "U1") (pin "20") (pinfunction "XIN_20") (pintype "bidirectional"))
      (node (ref "Y2") (pin "3") (pinfunction "2_3") (pintype "passive"))
    )
    (net (code "141") (name "Net-(U1-XOUT)") (class "Default")
      (node (ref "R10") (pin "2") (pinfunction "2_2") (pintype "passive"))
      (node (ref "U1") (pin "21") (pinfunction "XOUT_21") (pintype "bidirectional"))
    )
    (net (code "142") (name "Net-(U100A--IN)") (class "Default")
      (node (ref "C100") (pin "1") (pinfunction "1_1") (pintype "passive"))
      (node (ref "R104") (pin "1") (pinfunction "1_1") (pintype "passive"))
      (node (ref "R107") (pin "2") (pinfunction "2_2") (pintype "passive"))
      (node (ref "U100") (pin "2") (pinfunction "-IN_2") (pintype "input"))
    )
    (net (code "143") (name "Net-(U100B--IN)") (class "Default")
      (node (ref "U100") (pin "6") (pinfunction "-IN_6") (pintype "input"))
      (node (ref "U100") (pin "7") (pinfunction "OUT_7") (pintype "output"))
    )
    (net (code "144") (name "Net-(U101A--IN)") (class "Default")
      (node (ref "C102") (pin "1") (pinfunction "1_1") (pintype "passive"))
      (node (ref "R114") (pin "1") (pinfunction "1_1") (pintype "passive"))
      (node (ref "R115") (pin "2") (pinfunction "2_2") (pintype "passive"))
      (node (ref "U101") (pin "2") (pinfunction "-IN_2") (pintype "input"))
    )
    (net (code "145") (name "Net-(U101B--IN)") (class "Default")
      (node (ref "C104") (pin "1") (pinfunction "1_1") (pintype "passive"))
      (node (ref "R121") (pin "2") (pinfunction "2_2") (pintype "passive"))
      (node (ref "R123") (pin "1") (pinfunction "1_1") (pintype "passive"))
      (node (ref "U101") (pin "6") (pinfunction "-IN_6") (pintype "input"))
    )
    (net (code "146") (name "Net-(U102A--IN)") (class "Default")
      (node (ref "C106") (pin "1") (pinfunction "1_1") (pintype "passive"))
      (node (ref "R129") (pin "1") (pinfunction "1_1") (pintype "passive"))
      (node (ref "R132") (pin "2") (pinfunction "2_2") (pintype "passive"))
      (node (ref "U102") (pin "2") (pinfunction "-IN_2") (pintype "input"))
    )
    (net (code "147") (name "Net-(U102B--IN)") (class "Default")
      (node (ref "C108") (pin "1") (pinfunction "1_1") (pintype "passive"))
      (node (ref "R139") (pin "1") (pinfunction "1_1") (pintype "passive"))
      (node (ref "R140") (pin "2") (pinfunction "2_2") (pintype "passive"))
      (node (ref "U102") (pin "6") (pinfunction "-IN_6") (pintype "input"))
    )
    (net (code "148") (name "Net-(USB-D+)") (class "Default")
      (node (ref "R8") (pin "1") (pinfunction "1_1") (pintype "passive"))
      (node (ref "USB") (pin "3") (pinfunction "D+_3") (pintype "bidirectional"))
    )
    (net (code "149") (name "Net-(USB-D-)") (class "Default")
      (node (ref "R9") (pin "2") (pinfunction "2_2") (pintype "passive"))
      (node (ref "USB") (pin "2") (pinfunction "D-_2") (pintype "bidirectional"))
    )
    (net (code "150") (name "PLAY_B") (class "Default")
      (node (ref "JP4") (pin "9") (pinfunction "9_9") (pintype "passive"))
      (node (ref "U1") (pin "32") (pinfunction "GPIO21_32") (pintype "bidirectional"))
    )
    (net (code "151") (name "PLAY_T") (class "Default")
      (node (ref "JP102") (pin "9") (pinfunction "9_9") (pintype "passive"))
      (node (ref "PLAY") (pin "3") (pinfunction "3_3") (pintype "passive"))
      (node (ref "PLAY") (pin "4") (pinfunction "4_4") (pintype "passive"))
    )
    (net (code "152") (name "PRESE_CV_B") (class "Default")
      (node (ref "JP4") (pin "8") (pinfunction "8_8") (pintype "passive"))
      (node (ref "U1") (pin "41") (pinfunction "GPIO29/ADC3_41") (pintype "bidirectional"))
    )
    (net (code "153") (name "PRESE_CV_T") (class "Default")
      (node (ref "C100") (pin "2") (pinfunction "2_2") (pintype "passive"))
      (node (ref "JP102") (pin "8") (pinfunction "8_8") (pintype "passive"))
      (node (ref "R107") (pin "1") (pinfunction "1_1") (pintype "passive"))
      (node (ref "U100") (pin "1") (pinfunction "OUT_1") (pintype "output"))
    )
    (net (code "154") (name "PREST_B") (class "Default")
      (node (ref "JP4") (pin "7") (pinfunction "7_7") (pintype "passive"))
      (node (ref "U1") (pin "31") (pinfunction "GPIO20_31") (pintype "bidirectional"))
    )
    (net (code "155") (name "PREST_T") (class "Default")
      (node (ref "JP102") (pin "7") (pinfunction "7_7") (pintype "passive"))
      (node (ref "PRESET") (pin "1") (pinfunction "1_1") (pintype "passive"))
      (node (ref "PRESET") (pin "3") (pinfunction "3_3") (pintype "passive"))
    )
    (net (code "156") (name "RESE_CV_B") (class "Default")
      (node (ref "JP2") (pin "11") (pinfunction "11_11") (pintype "passive"))
      (node (ref "U1") (pin "13") (pinfunction "GPIO10_13") (pintype "bidirectional"))
    )
    (net (code "157") (name "RESE_CV_T") (class "Default")
      (node (ref "JP100") (pin "11") (pinfunction "11_11") (pintype "passive"))
      (node (ref "Q101") (pin "3") (pinfunction "C_3") (pintype "passive"))
      (node (ref "R108") (pin "1") (pinfunction "1_1") (pintype "passive"))
    )
    (net (code "158") (name "RUN") (class "Default")
      (node (ref "J1") (pin "10") (pinfunction "10_10") (pintype "passive"))
      (node (ref "R4") (pin "2") (pinfunction "2_2") (pintype "passive"))
      (node (ref "U1") (pin "26") (pinfunction "RUN_26") (pintype "bidirectional"))
    )
    (net (code "159") (name "ST{slash}SP_B") (class "Default")
      (node (ref "JP4") (pin "4") (pinfunction "4_4") (pintype "passive"))
      (node (ref "U1") (pin "18") (pinfunction "GPIO15_18") (pintype "bidirectional"))
    )
    (net (code "160") (name "ST{slash}SP_T") (class "Default")
      (node (ref "JP102") (pin "4") (pinfunction "4_4") (pintype "passive"))
      (node (ref "R109") (pin "2") (pinfunction "2_2") (pintype "passive"))
    )
    (net (code "161") (name "SWCLK") (class "Default")
      (node (ref "J1") (pin "4") (pinfunction "4_4") (pintype "passive"))
      (node (ref "JP1") (pin "2") (pinfunction "2_2") (pintype "passive"))
      (node (ref "U1") (pin "24") (pinfunction "SWCLK_24") (pintype "bidirectional"))
    )
    (net (code "162") (name "SWDI0") (class "Default")
      (node (ref "J1") (pin "2") (pinfunction "2_2") (pintype "passive"))
      (node (ref "JP1") (pin "3") (pinfunction "3_3") (pintype "passive"))
      (node (ref "U1") (pin "25") (pinfunction "SWDIO_25") (pintype "bidirectional"))
    )
    (net (code "163") (name "SYNC_CV_B") (class "Default")
      (node (ref "JP2") (pin "10") (pinfunction "10_10") (pintype "passive"))
      (node (ref "U1") (pin "12") (pinfunction "GPIO9_12") (pintype "bidirectional"))
    )
    (net (code "164") (name "SYNC_CV_T") (class "Default")
      (node (ref "JP100") (pin "10") (pinfunction "10_10") (pintype "passive"))
      (node (ref "Q102") (pin "3") (pinfunction "C_3") (pintype "passive"))
      (node (ref "R110") (pin "1") (pinfunction "1_1") (pintype "passive"))
    )
    (net (code "165") (name "TEMP_B") (class "Default")
      (node (ref "JP4") (pin "12") (pinfunction "12_12") (pintype "passive"))
      (node (ref "U1") (pin "36") (pinfunction "GPIO24_36") (pintype "bidirectional"))
    )
    (net (code "166") (name "TEMP_T") (class "Default")
      (node (ref "JP102") (pin "12") (pinfunction "12_12") (pintype "passive"))
      (node (ref "TEMPO") (pin "1") (pinfunction "1_1") (pintype "passive"))
      (node (ref "TEMPO") (pin "3") (pinfunction "3_3") (pintype "passive"))
    )
    (net (code "167") (name "unconnected-(+*--DO-PadDOUT)") (class "Default")
      (node (ref "+*-") (pin "DOUT") (pinfunction "DO_DOUT") (pintype "bidirectional"))
    )
    (net (code "168") (name "unconnected-(A_OUT-2-PadP2)") (class "Default")
      (node (ref "A_OUT") (pin "P2") (pinfunction "2_P2") (pintype "passive"))
    )
    (net (code "169") (name "unconnected-(B_OUT-2-PadP2)") (class "Default")
      (node (ref "B_OUT") (pin "P2") (pinfunction "2_P2") (pintype "passive"))
    )
    (net (code "170") (name "unconnected-(C_OUT-2-PadP2)") (class "Default")
      (node (ref "C_OUT") (pin "P2") (pinfunction "2_P2") (pintype "passive"))
    )
    (net (code "171") (name "unconnected-(D_OUT-2-PadP2)") (class "Default")
      (node (ref "D_OUT") (pin "P2") (pinfunction "2_P2") (pintype "passive"))
    )
    (net (code "172") (name "unconnected-(IC101-GPB7-Pad8)") (class "Default")
      (node (ref "IC101") (pin "8") (pinfunction "GPB7_8") (pintype "bidirectional"))
    )
    (net (code "173") (name "unconnected-(IC101-INTA-Pad20)") (class "Default")
      (node (ref "IC101") (pin "20") (pinfunction "INTA_20") (pintype "output"))
    )
    (net (code "174") (name "unconnected-(IC101-INTB-Pad19)") (class "Default")
      (node (ref "IC101") (pin "19") (pinfunction "INTB_19") (pintype "output"))
    )
    (net (code "175") (name "unconnected-(J1-Pad6)") (class "Default")
      (node (ref "J1") (pin "6") (pinfunction "6_6") (pintype "passive"))
    )
    (net (code "176") (name "unconnected-(J1-Pad7)") (class "Default")
      (node (ref "J1") (pin "7") (pinfunction "7_7") (pintype "passive"))
    )
    (net (code "177") (name "unconnected-(J1-Pad8)") (class "Default")
      (node (ref "J1") (pin "8") (pinfunction "8_8") (pintype "passive"))
    )
    (net (code "178") (name "unconnected-(RESE-2-PadP2)") (class "Default")
      (node (ref "RESE") (pin "P2") (pinfunction "2_P2") (pintype "passive"))
    )
    (net (code "179") (name "unconnected-(ST/SP-2-PadP2)") (class "Default")
      (node (ref "ST/SP") (pin "P2") (pinfunction "2_P2") (pintype "passive"))
    )
    (net (code "180") (name "unconnected-(SYNC-2-PadP2)") (class "Default")
      (node (ref "SYNC") (pin "P2") (pinfunction "2_P2") (pintype "passive"))
    )
    (net (code "181") (name "unconnected-(USB-ID-Pad4)") (class "Default")
      (node (ref "USB") (pin "4") (pinfunction "ID_4") (pintype "bidirectional"))
    )
    (net (code "182") (name "unconnected-(USB-VCC-Pad1)") (class "Default")
      (node (ref "USB") (pin "1") (pinfunction "VCC_1") (pintype "bidirectional"))
    )
  )
)
